# Dual-MCU-control-board.net
KiCad netlist of a schematic drawn in Altium Designer
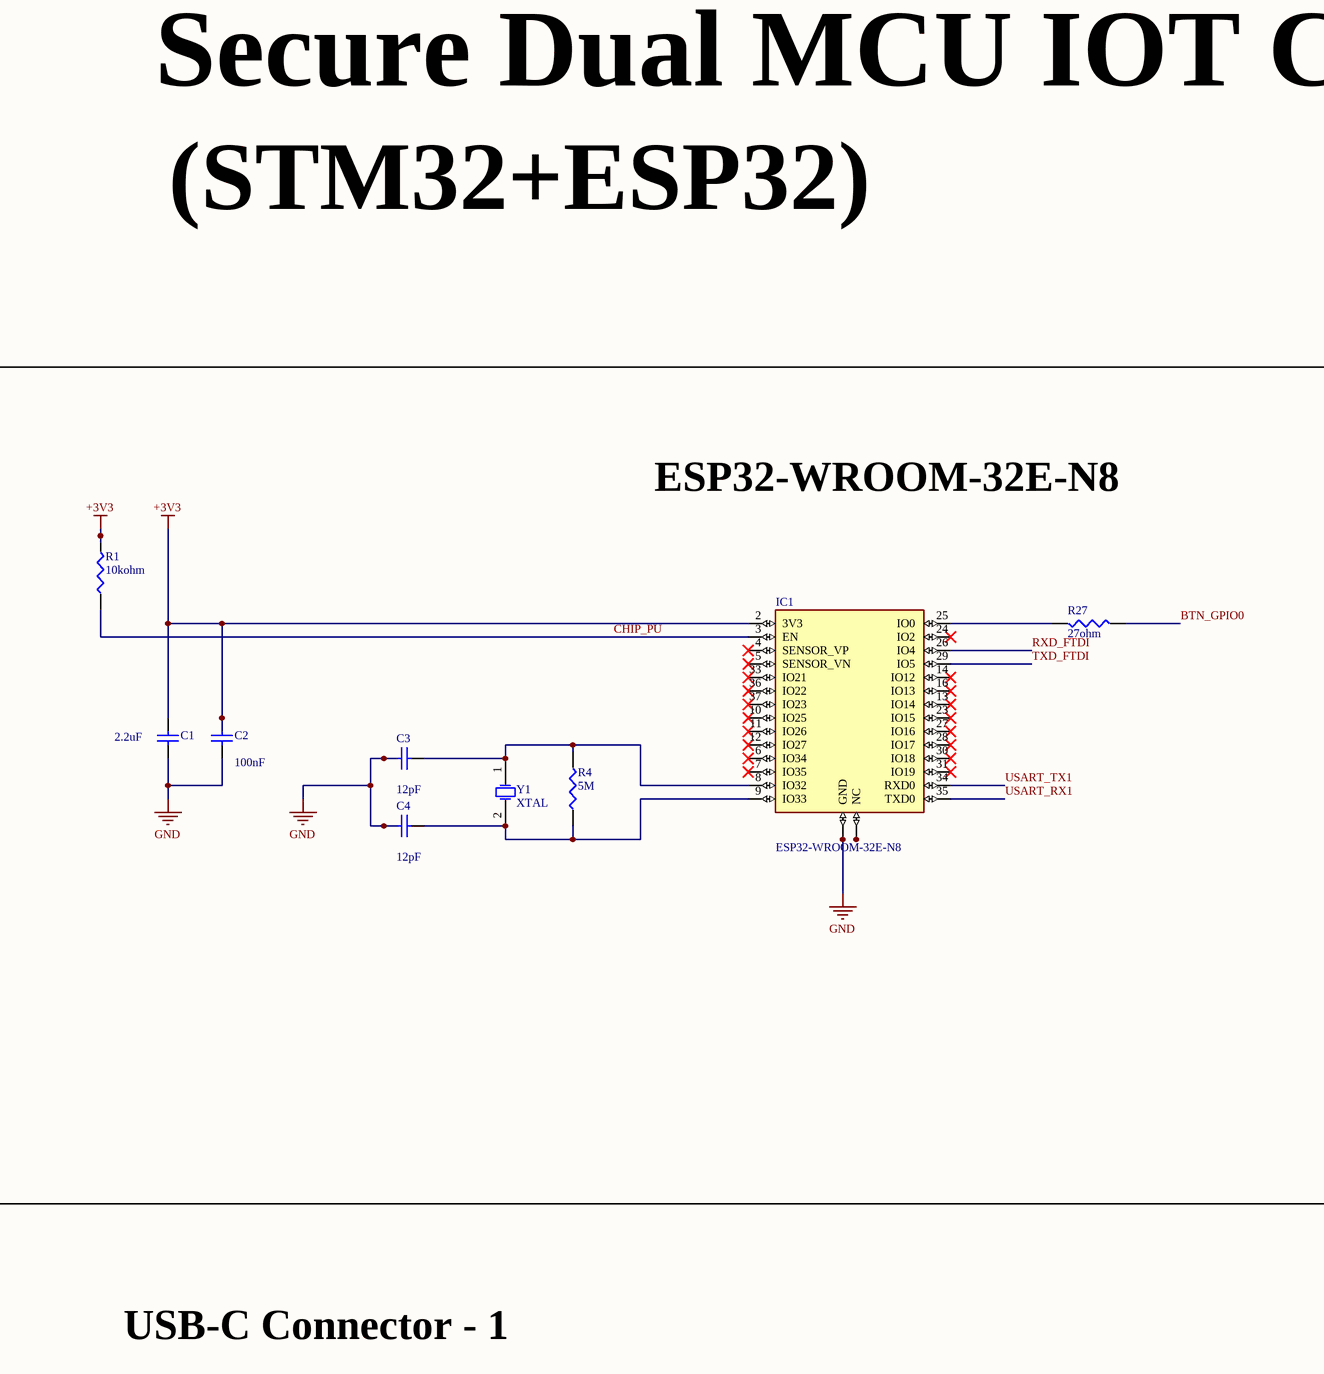
[diagram p0: Dual-MCU-control-board.SchDoc, top left]
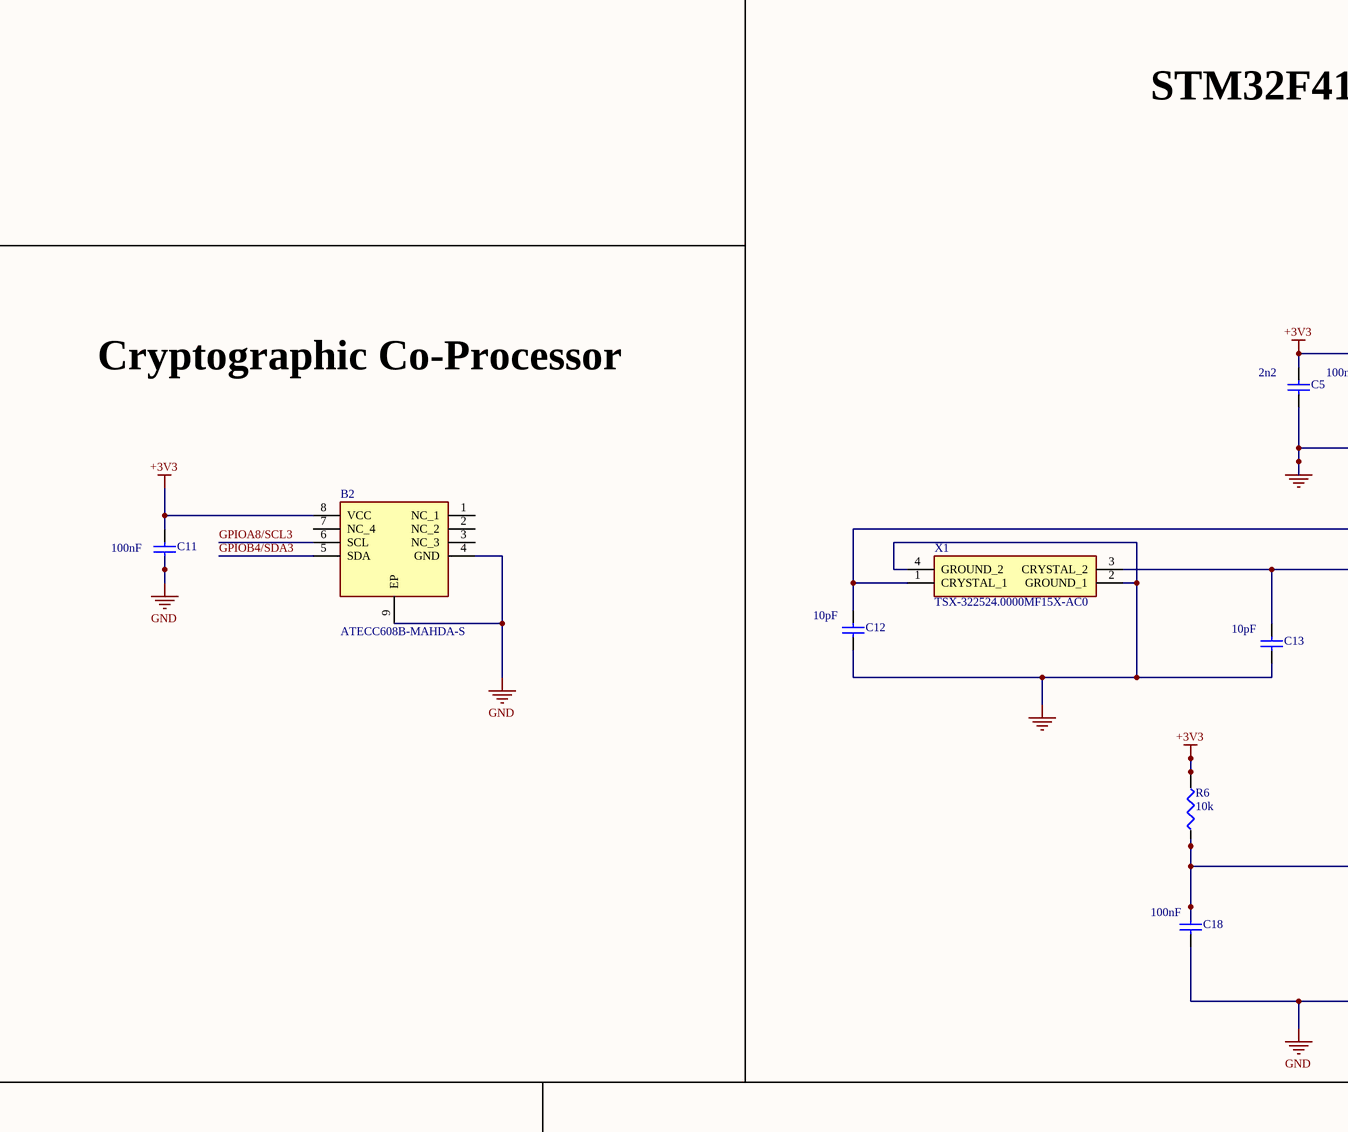
[diagram p1: Dual-MCU-control-board.SchDoc, top middle]
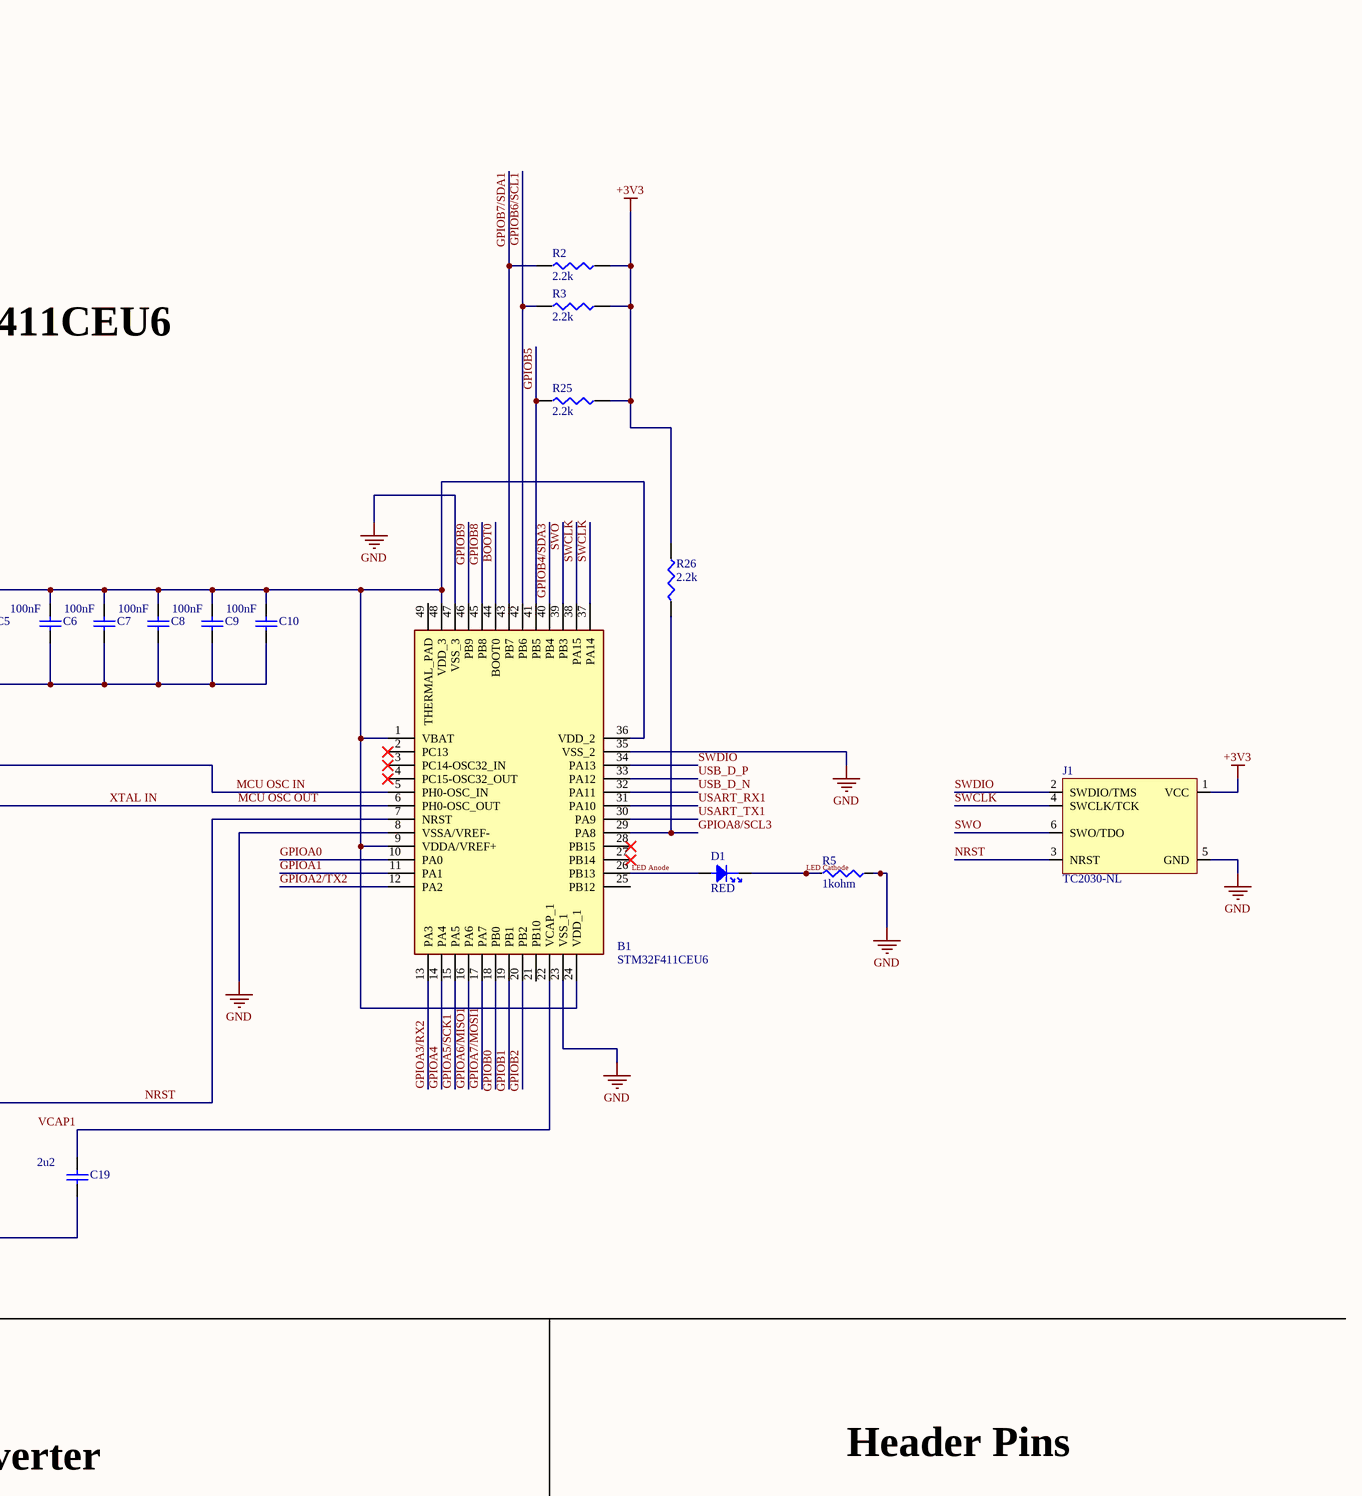
[diagram p2: Dual-MCU-control-board.SchDoc, top right]
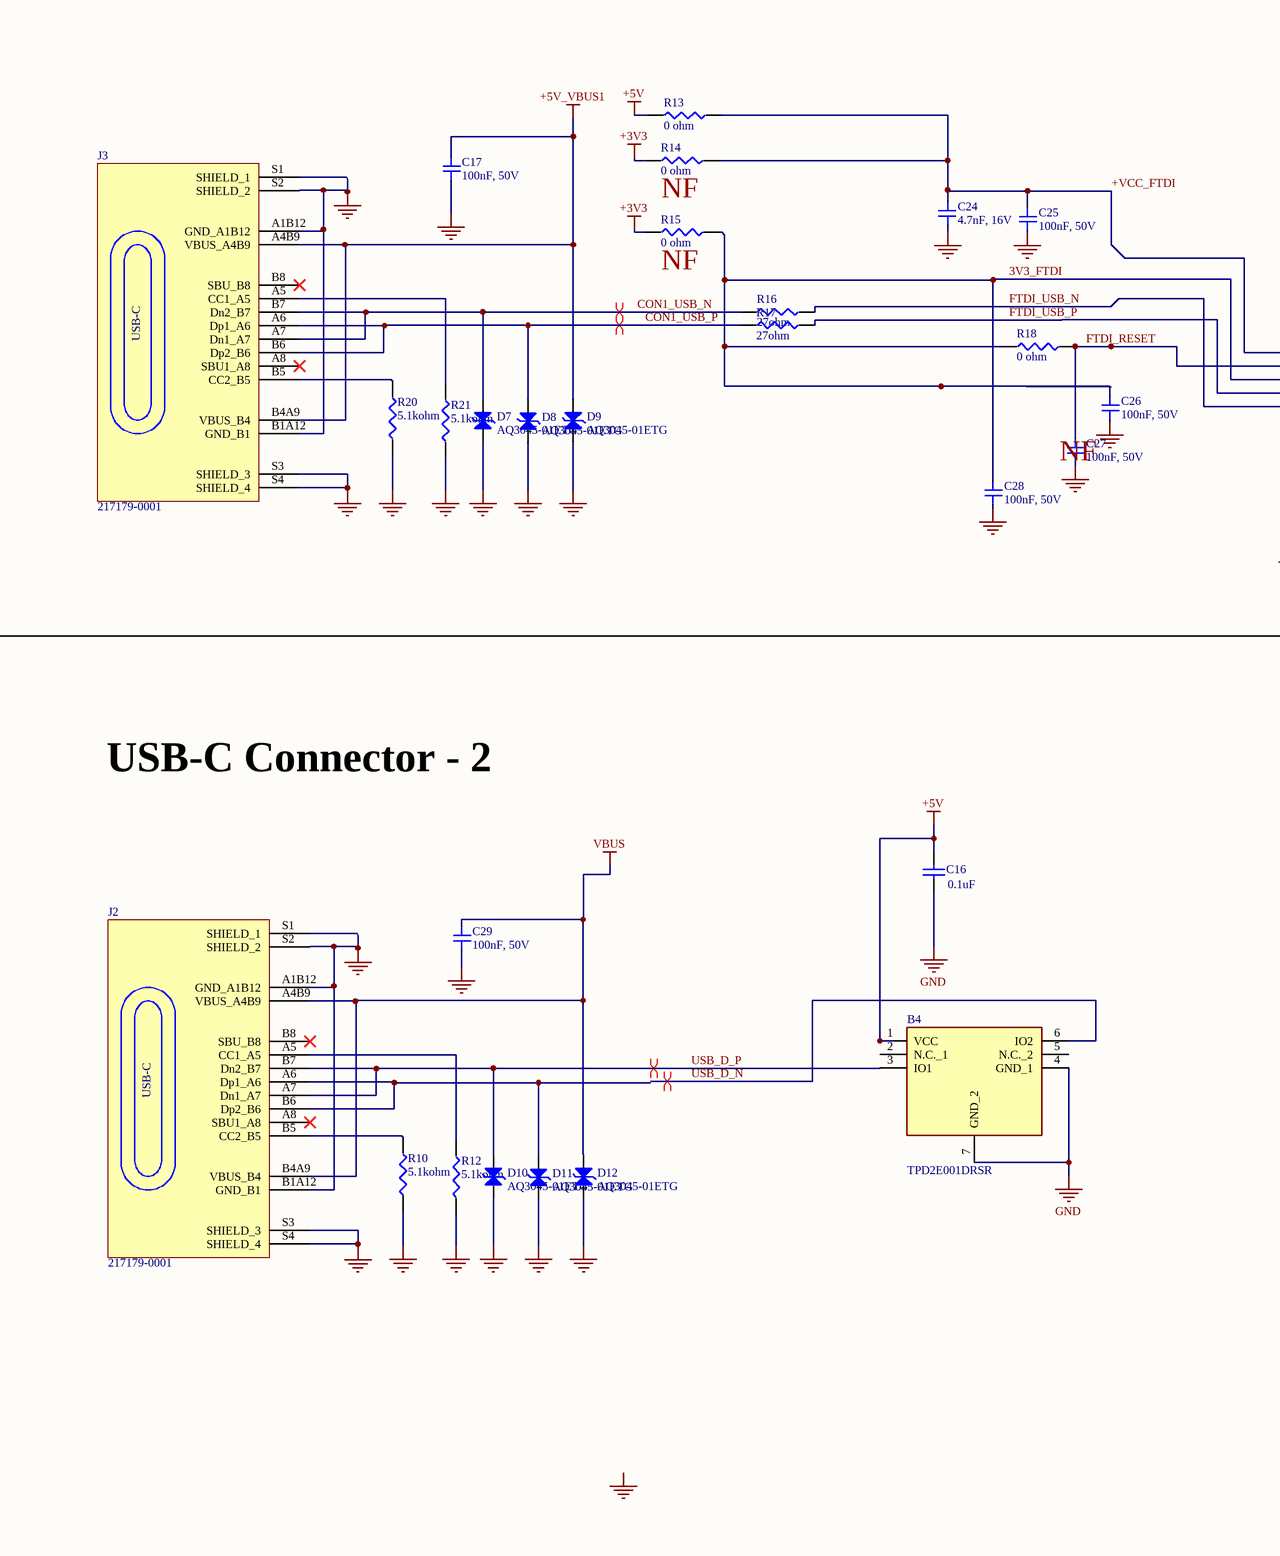
[diagram p3: Dual-MCU-control-board.SchDoc, bottom left]
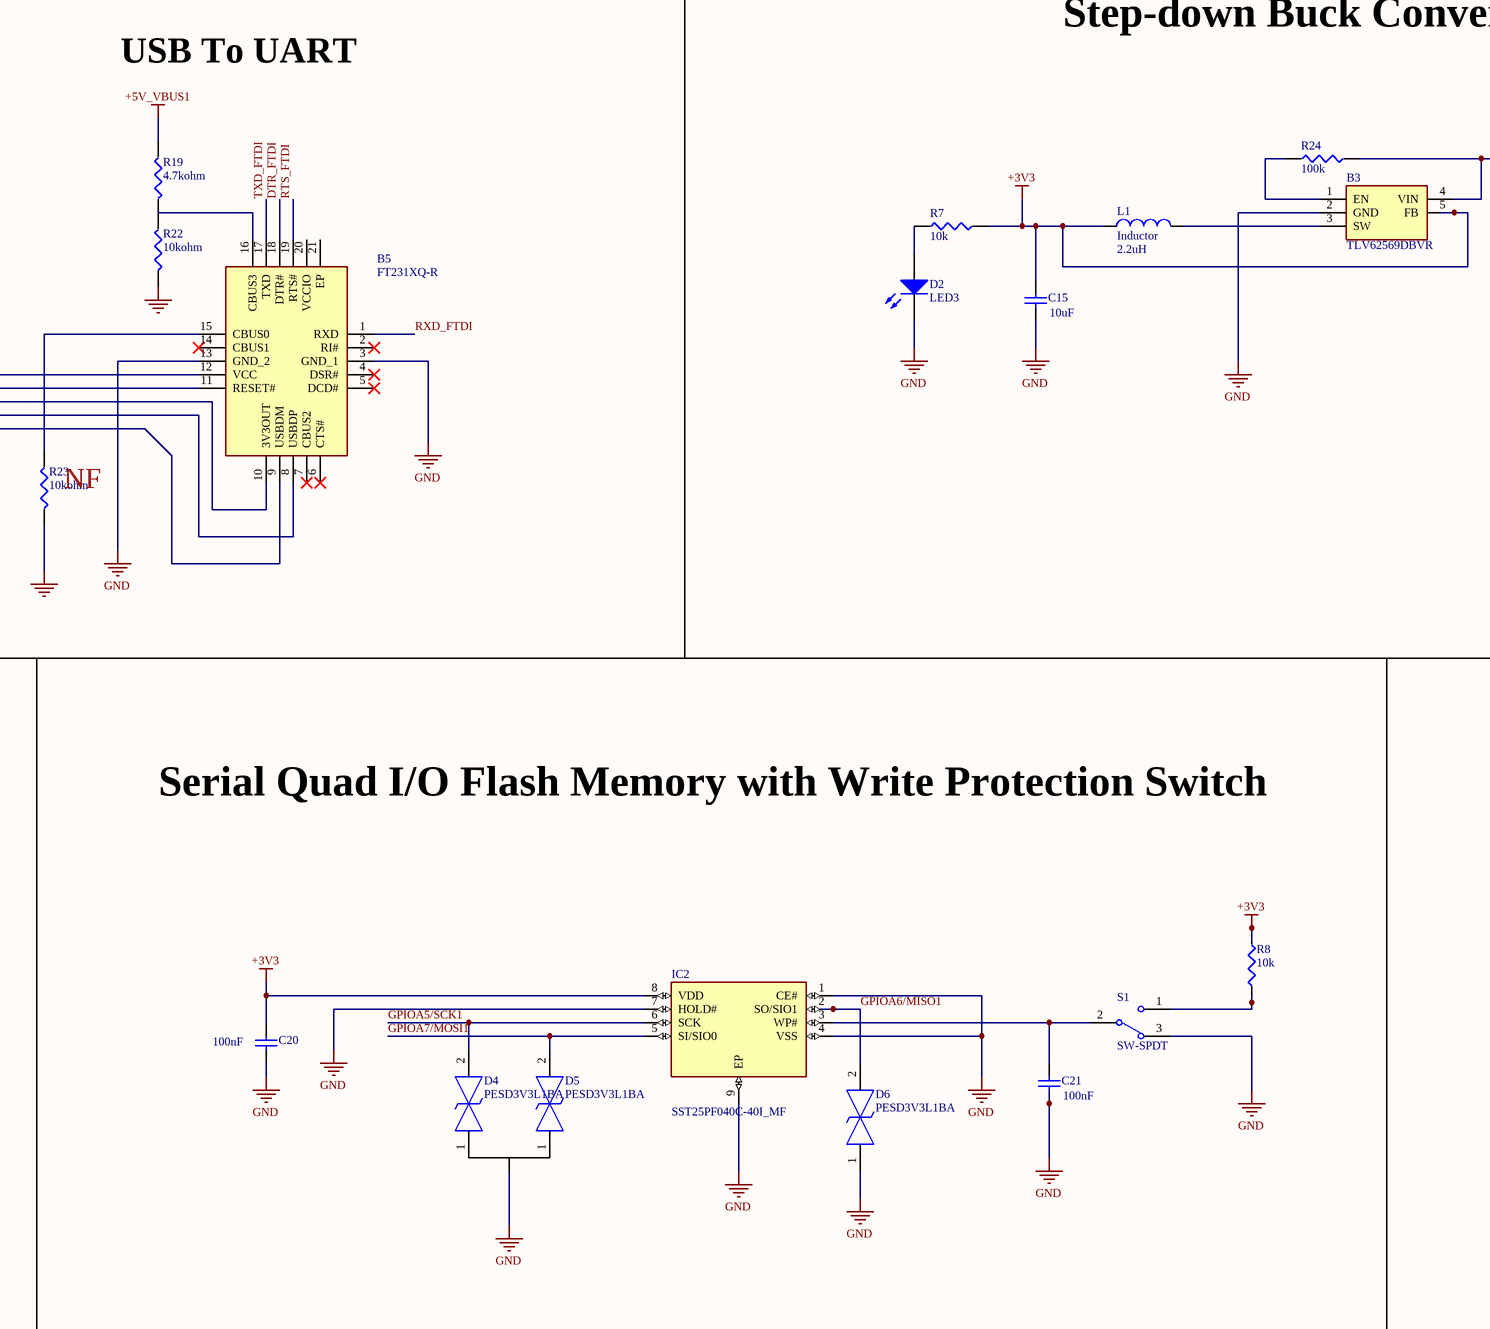
[diagram p4: Dual-MCU-control-board.SchDoc, bottom middle]
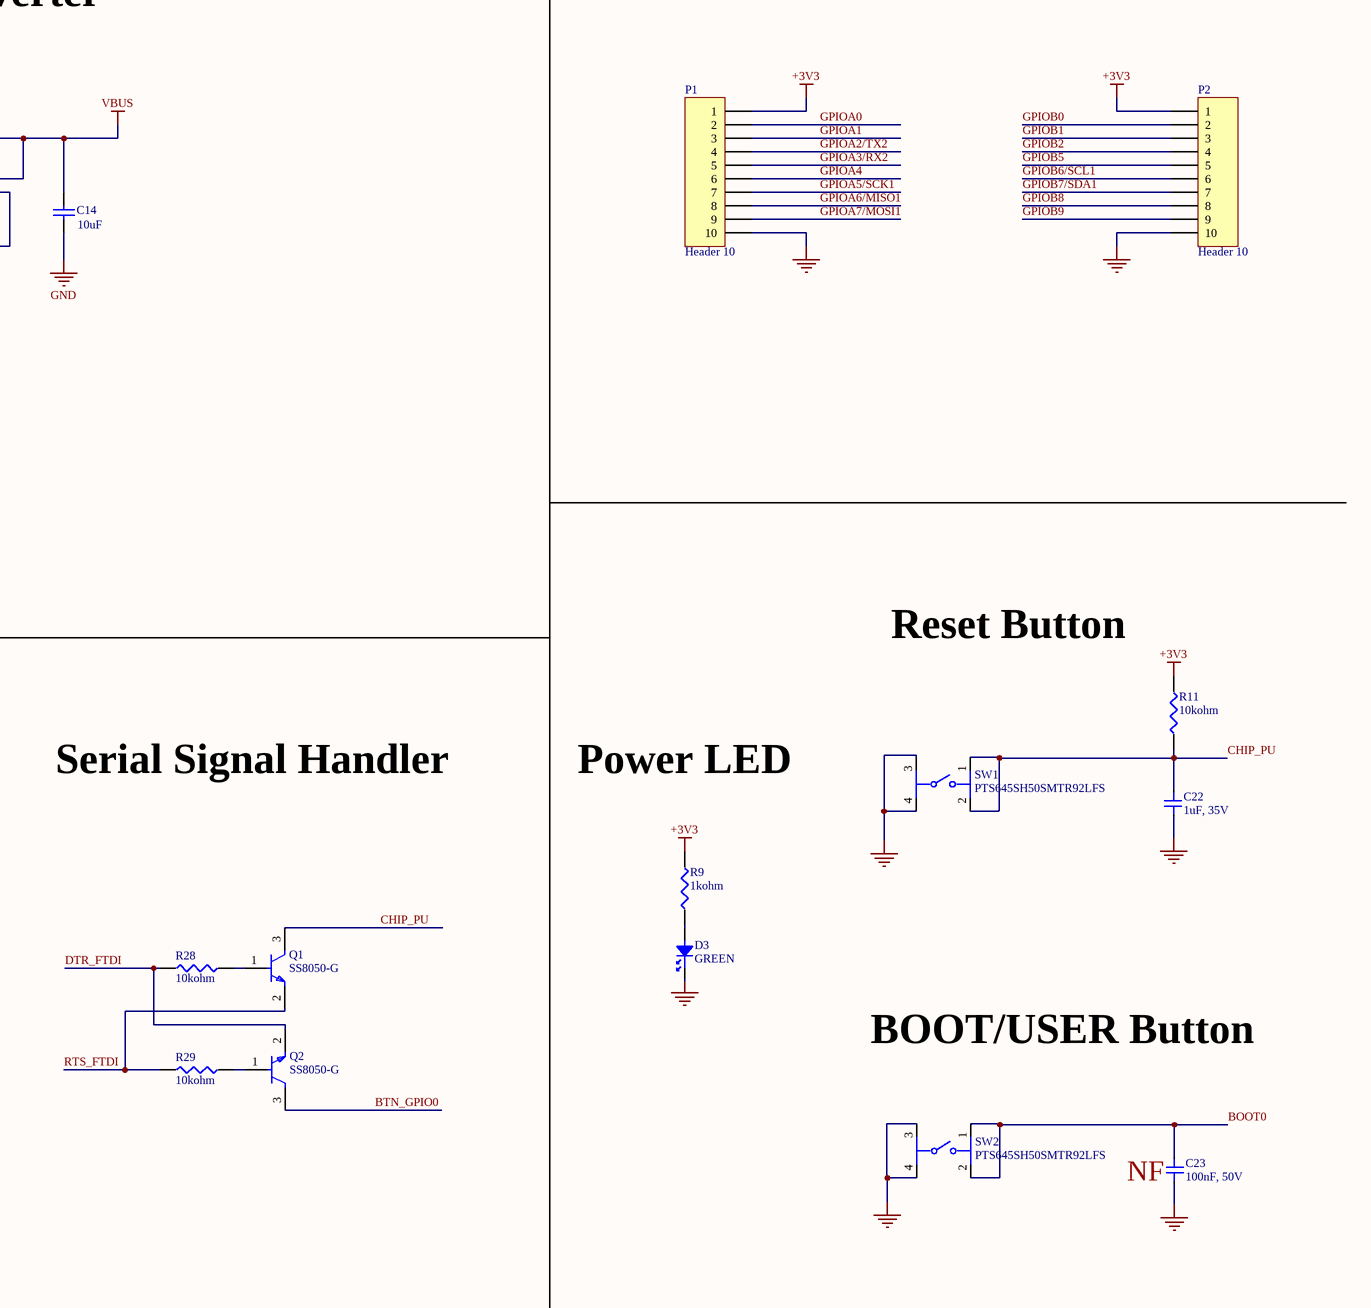
[diagram p5: Dual-MCU-control-board.SchDoc, bottom right]

(export (version "E")
  (design (tool "Eeschema 10.0.6"))
  (components
    (comp (ref "B1")
      (value "STM32F411CEU6")
      (footprint "QFN50P700X700X60-49N-D")
      (fields (field (name "MOUSER PART NUMBER") "511-STM32F411CEU6"))
      (libsource (lib "STM32F411CEU6") (part "STM32F411CEU6"))
    )
    (comp (ref "B2")
      (value "ATECC608B-MAHDA-S")
      (footprint "SON50P300X200X60-9N")
      (description "Security ICs / Authentication ICs ECC/ECDH, I2C, small 3K reel UDFN")
      (fields (field (name "MOUSER PART NUMBER") "579-TECC608B-MAHDA-S"))
      (libsource (lib "ATECC608B-MAHDA-S") (part "ATECC608B-MAHDA-S"))
    )
    (comp (ref "B3")
      (value "TLV62569DBVR")
      (footprint "SOT95P280X145-5N")
      (description "2.5V-5.5V input, 2-A high efficiency step-down buck converter in SOT23 and SOT563 package")
      (fields (field (name "MOUSER PART NUMBER") "595-TLV62569DBVR"))
      (libsource (lib "TLV62569DBVR") (part "TLV62569DBVR"))
    )
    (comp (ref "B4")
      (value "TPD2E001DRSR")
      (footprint "SON95P300X300X80-7N-D")
      (description "TPD2E001 LOW-CAPACITANCE 2-CHANNEL +/-15-kV ESD-PROTECTION ARRAY FOR HIGH-SPEED DATA INTERFACES")
      (fields (field (name "MOUSER PART NUMBER") "595-TPD2E001DRSR"))
      (libsource (lib "TPD2E001DRSR") (part "TPD2E001DRSR"))
    )
    (comp (ref "B5")
      (value "FT231XQ-R")
      (footprint "QFN50P400X400X80-21N")
      (description "FTDI Chip FT231XQ-R, USB Transceiver")
      (fields (field (name "MOUSER PART NUMBER") "895-FT231XQ-R"))
      (libsource (lib "FT231XQ-R") (part "FT231XQ-R"))
    )
    (comp (ref "C1")
      (value "2.2uF")
      (footprint "C1206")
      (description "Capacitor (Semiconductor SIM Model)")
      (fields (field (name "Comment") "Cap Semi") (field (name "PUBLISHER") "Altium Limited"))
      (libsource (lib "Miscellaneous Devices") (part "Cap Semi"))
    )
    (comp (ref "C2")
      (value "100nF")
      (footprint "C1206")
      (description "Capacitor (Semiconductor SIM Model)")
      (fields (field (name "Comment") "Cap Semi") (field (name "PUBLISHER") "Altium Limited"))
      (libsource (lib "Miscellaneous Devices") (part "Cap Semi"))
    )
    (comp (ref "C3")
      (value "12pF")
      (footprint "C1206")
      (description "Capacitor (Semiconductor SIM Model)")
      (fields (field (name "Comment") "Cap Semi") (field (name "PUBLISHER") "Altium Limited"))
      (libsource (lib "Miscellaneous Devices") (part "Cap Semi"))
    )
    (comp (ref "C4")
      (value "12pF")
      (footprint "C1206")
      (description "Capacitor (Semiconductor SIM Model)")
      (fields (field (name "Comment") "Cap Semi") (field (name "PUBLISHER") "Altium Limited"))
      (libsource (lib "Miscellaneous Devices") (part "Cap Semi"))
    )
    (comp (ref "C5")
      (value "2n2")
      (footprint "C1206")
      (description "Capacitor (Semiconductor SIM Model)")
      (fields (field (name "Comment") "Cap Semi") (field (name "PUBLISHER") "Altium Limited"))
      (libsource (lib "Miscellaneous Devices") (part "Cap Semi"))
    )
    (comp (ref "C6")
      (value "100nF")
      (footprint "C1206")
      (description "Capacitor (Semiconductor SIM Model)")
      (fields (field (name "Comment") "Cap Semi") (field (name "PUBLISHER") "Altium Limited"))
      (libsource (lib "Miscellaneous Devices") (part "Cap Semi"))
    )
    (comp (ref "C7")
      (value "100nF")
      (footprint "C1206")
      (description "Capacitor (Semiconductor SIM Model)")
      (fields (field (name "Comment") "Cap Semi") (field (name "PUBLISHER") "Altium Limited"))
      (libsource (lib "Miscellaneous Devices") (part "Cap Semi"))
    )
    (comp (ref "C8")
      (value "100nF")
      (footprint "C1206")
      (description "Capacitor (Semiconductor SIM Model)")
      (fields (field (name "Comment") "Cap Semi") (field (name "PUBLISHER") "Altium Limited"))
      (libsource (lib "Miscellaneous Devices") (part "Cap Semi"))
    )
    (comp (ref "C9")
      (value "100nF")
      (footprint "C1206")
      (description "Capacitor (Semiconductor SIM Model)")
      (fields (field (name "Comment") "Cap Semi") (field (name "PUBLISHER") "Altium Limited"))
      (libsource (lib "Miscellaneous Devices") (part "Cap Semi"))
    )
    (comp (ref "C10")
      (value "100nF")
      (footprint "C1206")
      (description "Capacitor (Semiconductor SIM Model)")
      (fields (field (name "Comment") "Cap Semi") (field (name "PUBLISHER") "Altium Limited"))
      (libsource (lib "Miscellaneous Devices") (part "Cap Semi"))
    )
    (comp (ref "C11")
      (value "100nF")
      (footprint "C1206")
      (description "Capacitor (Semiconductor SIM Model)")
      (fields (field (name "Comment") "Cap Semi") (field (name "PUBLISHER") "Altium Limited"))
      (libsource (lib "Miscellaneous Devices") (part "Cap Semi"))
    )
    (comp (ref "C12")
      (value "10pF")
      (footprint "C1206")
      (description "Capacitor (Semiconductor SIM Model)")
      (fields (field (name "Comment") "Cap Semi") (field (name "PUBLISHER") "Altium Limited"))
      (libsource (lib "Miscellaneous Devices") (part "Cap Semi"))
    )
    (comp (ref "C13")
      (value "10pF")
      (footprint "C1206")
      (description "Capacitor (Semiconductor SIM Model)")
      (fields (field (name "Comment") "Cap Semi") (field (name "PUBLISHER") "Altium Limited"))
      (libsource (lib "Miscellaneous Devices") (part "Cap Semi"))
    )
    (comp (ref "C14")
      (value "10uF")
      (footprint "C1206")
      (description "Capacitor (Semiconductor SIM Model)")
      (fields (field (name "Comment") "Cap Semi") (field (name "PUBLISHER") "Altium Limited"))
      (libsource (lib "Miscellaneous Devices") (part "Cap Semi"))
    )
    (comp (ref "C15")
      (value "10uF")
      (footprint "C1206")
      (description "Capacitor (Semiconductor SIM Model)")
      (fields (field (name "Comment") "Cap Semi") (field (name "PUBLISHER") "Altium Limited"))
      (libsource (lib "Miscellaneous Devices") (part "Cap Semi"))
    )
    (comp (ref "C16")
      (value "0.1uF")
      (footprint "C1206")
      (description "Capacitor (Semiconductor SIM Model)")
      (fields (field (name "Comment") "Cap Semi") (field (name "PUBLISHER") "Altium Limited"))
      (libsource (lib "Miscellaneous Devices") (part "Cap Semi"))
    )
    (comp (ref "C17")
      (value "100nF, 50V")
      (footprint "CAPC1005X55N")
      (description "CAP CER 0.1UF 50V X7R 0402")
      (fields
        (field (name "MANUFACTURER") "Samsung")
        (field (name "MANUFACTURER PART NUMBER") "CL05B104KB54PNC")
      )
      (libsource (lib "Schlib") (part "CL05B104KB54PNC"))
    )
    (comp (ref "C18")
      (value "100nF")
      (footprint "C1206")
      (description "Capacitor (Semiconductor SIM Model)")
      (fields (field (name "Comment") "Cap Semi") (field (name "PUBLISHER") "Altium Limited"))
      (libsource (lib "Miscellaneous Devices") (part "Cap Semi"))
    )
    (comp (ref "C19")
      (value "2u2")
      (footprint "C1206")
      (description "Capacitor (Semiconductor SIM Model)")
      (fields (field (name "Comment") "Cap Semi") (field (name "PUBLISHER") "Altium Limited"))
      (libsource (lib "Miscellaneous Devices") (part "Cap Semi"))
    )
    (comp (ref "C20")
      (value "100nF")
      (footprint "C1206")
      (description "Capacitor (Semiconductor SIM Model)")
      (fields (field (name "Comment") "Cap Semi") (field (name "PUBLISHER") "Altium Limited"))
      (libsource (lib "Miscellaneous Devices") (part "Cap Semi"))
    )
    (comp (ref "C21")
      (value "100nF")
      (footprint "C1206")
      (description "Capacitor (Semiconductor SIM Model)")
      (fields (field (name "Comment") "Cap Semi") (field (name "PUBLISHER") "Altium Limited"))
      (libsource (lib "Miscellaneous Devices") (part "Cap Semi"))
    )
    (comp (ref "C22")
      (value "1uF, 35V")
      (footprint "CAPC1005X55N")
      (description "CAP CER 1UF 35V X5R 0402")
      (fields
        (field (name "MANUFACTURER") "Samsung")
        (field (name "MANUFACTURER PART NUMBER") "CL05A105KL5NRNC")
      )
      (libsource (lib "Schlib") (part "CL05A105KL5NRNC"))
    )
    (comp (ref "C23")
      (value "100nF, 50V")
      (footprint "CAPC1005X55N")
      (description "CAP CER 0.1UF 50V X7R 0402")
      (fields
        (field (name "MANUFACTURER") "Samsung")
        (field (name "MANUFACTURER PART NUMBER") "CL05B104KB54PNC")
      )
      (libsource (lib "Schlib") (part "CL05B104KB54PNC"))
    )
    (comp (ref "C24")
      (value "4.7nF, 16V")
      (footprint "CAPC1005X55N")
      (description "CAP CER 0402 4.7NF 16V X7R 10%")
      (fields
        (field (name "MANUFACTURER") "KEMET")
        (field (name "MANUFACTURER PART NUMBER") "C0402C472K4RECAUTO")
      )
      (libsource (lib "Schlib") (part "C0402C472K4RECAUTO"))
    )
    (comp (ref "C25")
      (value "100nF, 50V")
      (footprint "CAPC1005X55N")
      (description "CAP CER 0.1UF 50V X7R 0402")
      (fields
        (field (name "MANUFACTURER") "Samsung")
        (field (name "MANUFACTURER PART NUMBER") "CL05B104KB54PNC")
      )
      (libsource (lib "Schlib") (part "CL05B104KB54PNC"))
    )
    (comp (ref "C26")
      (value "100nF, 50V")
      (footprint "CAPC1005X55N")
      (description "CAP CER 0.1UF 50V X7R 0402")
      (fields
        (field (name "MANUFACTURER") "Samsung")
        (field (name "MANUFACTURER PART NUMBER") "CL05B104KB54PNC")
      )
      (libsource (lib "Schlib") (part "CL05B104KB54PNC"))
    )
    (comp (ref "C27")
      (value "100nF, 50V")
      (footprint "CAPC1005X55N")
      (description "CAP CER 0.1UF 50V X7R 0402")
      (fields
        (field (name "MANUFACTURER") "Samsung")
        (field (name "MANUFACTURER PART NUMBER") "CL05B104KB54PNC")
      )
      (libsource (lib "Schlib") (part "CL05B104KB54PNC"))
    )
    (comp (ref "C28")
      (value "100nF, 50V")
      (footprint "CAPC1005X55N")
      (description "CAP CER 0.1UF 50V X7R 0402")
      (fields
        (field (name "MANUFACTURER") "Samsung")
        (field (name "MANUFACTURER PART NUMBER") "CL05B104KB54PNC")
      )
      (libsource (lib "Schlib") (part "CL05B104KB54PNC"))
    )
    (comp (ref "C29")
      (value "100nF, 50V")
      (footprint "CAPC1005X55N")
      (description "CAP CER 0.1UF 50V X7R 0402")
      (fields
        (field (name "MANUFACTURER") "Samsung")
        (field (name "MANUFACTURER PART NUMBER") "CL05B104KB54PNC")
      )
      (libsource (lib "Schlib") (part "CL05B104KB54PNC"))
    )
    (comp (ref "D1")
      (value "RED")
      (footprint "LEDC1005X35N")
      (description "Single Color LED, Super Red, 0.5mm")
      (fields
        (field (name "MANUFACTURER") "Vishay")
        (field (name "MANUFACTURER PART NUMBER") "VLMS1500-GS08")
      )
      (libsource (lib "Schlib") (part "VLMS1500-GS08"))
    )
    (comp (ref "D2")
      (value "LED3")
      (footprint "3.5X2.8X1.9")
      (description "Typical BLUE SiC LED")
      (fields (field (name "PUBLISHER") "Altium Limited"))
      (libsource (lib "Miscellaneous Devices") (part "LED3"))
    )
    (comp (ref "D3")
      (value "GREEN")
      (footprint "LEDC1005X35N")
      (description "Single Color LED, Yellow Green, 0.5mm")
      (fields
        (field (name "MANUFACTURER") "Vishay")
        (field (name "MANUFACTURER PART NUMBER") "VLMG1500-GS08")
      )
      (libsource (lib "Schlib") (part "VLMG1500-GS08"))
    )
    (comp (ref "D4")
      (value "PESD3V3L1BA")
      (footprint "SOD2512X110N")
      (description "TVS Diode Bi-Directional PESD3V3L1BA 26V, 500W, UMD 2-Pin")
      (libsource (lib "PESD3V3L1BA") (part "PESD3V3L1BA"))
    )
    (comp (ref "D5")
      (value "PESD3V3L1BA")
      (footprint "SOD2512X110N")
      (description "TVS Diode Bi-Directional PESD3V3L1BA 26V, 500W, UMD 2-Pin")
      (libsource (lib "PESD3V3L1BA") (part "PESD3V3L1BA"))
    )
    (comp (ref "D6")
      (value "PESD3V3L1BA")
      (footprint "SOD2512X110N")
      (description "TVS Diode Bi-Directional PESD3V3L1BA 26V, 500W, UMD 2-Pin")
      (libsource (lib "PESD3V3L1BA") (part "PESD3V3L1BA"))
    )
    (comp (ref "D7")
      (value "AQ3045-01ETG")
      (footprint "SOD882")
      (description "TVS DIODE 5.3VWM 12VC SOD882")
      (fields (field (name "MANUFACTURER") "Littelfuse") (field (name "LCSC PART NUMBER") "C3710326"))
      (libsource (lib "Schlib") (part "AQ3045-01ETG"))
    )
    (comp (ref "D8")
      (value "AQ3045-01ETG")
      (footprint "SOD882")
      (description "TVS DIODE 5.3VWM 12VC SOD882")
      (fields (field (name "MANUFACTURER") "Littelfuse") (field (name "LCSC PART NUMBER") "C3710326"))
      (libsource (lib "Schlib") (part "AQ3045-01ETG"))
    )
    (comp (ref "D9")
      (value "AQ3045-01ETG")
      (footprint "SOD882")
      (description "TVS DIODE 5.3VWM 12VC SOD882")
      (fields (field (name "MANUFACTURER") "Littelfuse") (field (name "LCSC PART NUMBER") "C3710326"))
      (libsource (lib "Schlib") (part "AQ3045-01ETG"))
    )
    (comp (ref "D10")
      (value "AQ3045-01ETG")
      (footprint "SOD882")
      (description "TVS DIODE 5.3VWM 12VC SOD882")
      (fields (field (name "MANUFACTURER") "Littelfuse") (field (name "LCSC PART NUMBER") "C3710326"))
      (libsource (lib "Schlib") (part "AQ3045-01ETG"))
    )
    (comp (ref "D11")
      (value "AQ3045-01ETG")
      (footprint "SOD882")
      (description "TVS DIODE 5.3VWM 12VC SOD882")
      (fields (field (name "MANUFACTURER") "Littelfuse") (field (name "LCSC PART NUMBER") "C3710326"))
      (libsource (lib "Schlib") (part "AQ3045-01ETG"))
    )
    (comp (ref "D12")
      (value "AQ3045-01ETG")
      (footprint "SOD882")
      (description "TVS DIODE 5.3VWM 12VC SOD882")
      (fields (field (name "MANUFACTURER") "Littelfuse") (field (name "LCSC PART NUMBER") "C3710326"))
      (libsource (lib "Schlib") (part "AQ3045-01ETG"))
    )
    (comp (ref "IC1")
      (value "ESP32-WROOM-32E-N8")
      (footprint "ESP32WROOM32EN8")
      (fields (field (name "MF") "Espressif Systems"))
      (libsource (lib "ESP32-WROOM-32E-N8") (part "ESP32-WROOM-32E-N8"))
    )
    (comp (ref "IC2")
      (value "SST25PF040C-40I_MF")
      (footprint "SON127P600X500X80-9N")
      (description "FLASH Memory IC 4Mb (512K x 8) SPI 40 MHz 8-WDFN (5x6)")
      (fields (field (name "MF") "Microchip") (field (name "MP") "SST25PF040C-40I/MF"))
      (libsource (lib "SST25PF040C-40I_MF") (part "SST25PF040C-40I_MF"))
    )
    (comp (ref "J1")
      (value "TC2030-NL")
      (footprint "TC2030-NL-FP")
      (description "Tag-Connect No-Solder SWD Debug Connector (No Legs) DO NOT PLACE")
      (fields
        (field (name "MANUFACTURER") "Tag-Connect")
        (field (name "MANUFACTURER PART NUMBER") "TC2030-NL-FP")
      )
      (libsource (lib "Schematic-Lib-PhilsLab") (part "TC2030-NL"))
    )
    (comp (ref "J2")
      (value "217179-0001")
      (footprint "FP-2171790001-MFG")
      (description "CONN RCP USB2.0 TYP C 24P SMD RA")
      (fields (field (name "MANUFACTURER") "Molex"))
      (libsource (lib "Schlib") (part "217179-0001"))
    )
    (comp (ref "J3")
      (value "217179-0001")
      (footprint "FP-2171790001-MFG")
      (description "CONN RCP USB2.0 TYP C 24P SMD RA")
      (fields (field (name "MANUFACTURER") "Molex"))
      (libsource (lib "Schlib") (part "217179-0001"))
    )
    (comp (ref "L1")
      (value "Inductor")
      (footprint "0402-A")
      (fields (field (name "ALTIUM_VALUE") "2.2uH") (field (name "PUBLISHER") "Altium Limited"))
      (libsource (lib "Miscellaneous Devices") (part "Inductor"))
    )
    (comp (ref "P1")
      (value "Header 10")
      (footprint "HDR1X10")
      (description "Header, 10-Pin")
      (fields (field (name "PUBLISHER") "Altium Limited"))
      (libsource (lib "") (part "Header 10_1"))
    )
    (comp (ref "P2")
      (value "Header 10")
      (footprint "HDR1X10")
      (description "Header, 10-Pin")
      (fields (field (name "PUBLISHER") "Altium Limited"))
      (libsource (lib "Miscellaneous Connectors") (part "Header 10"))
    )
    (comp (ref "Q1")
      (value "SS8050-G")
      (footprint "FP-SS8050-G-IPC_B")
      (description "TRANS NPN 25V 1.5A SOT-23-3")
      (fields (field (name "MANUFACTURER") "Comchip") (field (name "LCSC PART NUMBER") "C164886"))
      (libsource (lib "Schlib") (part "SS8050-G"))
    )
    (comp (ref "Q2")
      (value "SS8050-G")
      (footprint "FP-SS8050-G-IPC_B")
      (description "TRANS NPN 25V 1.5A SOT-23-3")
      (fields (field (name "MANUFACTURER") "Comchip") (field (name "LCSC PART NUMBER") "C164886"))
      (libsource (lib "Schlib") (part "SS8050-G"))
    )
    (comp (ref "R1")
      (value "10kohm")
      (footprint "RESC1005X37N")
      (description "RES 10K OHM 1% 1/16W 0402")
      (fields
        (field (name "MANUFACTURER") "Yageo")
        (field (name "MANUFACTURER PART NUMBER") "RC0402FR-07100KL")
      )
      (libsource (lib "Schlib") (part "RC0402FR-07100KL"))
    )
    (comp (ref "R2")
      (value "2.2k")
      (footprint "RESC1005X37N")
      (description "RES 1K OHM 1% 1/16W 0402")
      (fields
        (field (name "MANUFACTURER") "Yageo")
        (field (name "MANUFACTURER PART NUMBER") "RC0402FR-071KL")
      )
      (libsource (lib "Schlib") (part "RC0402FR-071KL"))
    )
    (comp (ref "R3")
      (value "2.2k")
      (footprint "RESC1005X37N")
      (description "RES 1K OHM 1% 1/16W 0402")
      (fields
        (field (name "MANUFACTURER") "Yageo")
        (field (name "MANUFACTURER PART NUMBER") "RC0402FR-071KL")
      )
      (libsource (lib "Schlib") (part "RC0402FR-071KL"))
    )
    (comp (ref "R4")
      (value "5M")
      (footprint "RESC1005X37N")
      (description "RES 4.7K OHM 1% 1/16W 0402")
      (fields
        (field (name "MANUFACTURER") "Yageo")
        (field (name "MANUFACTURER PART NUMBER") "RC0402FR-074K7L")
      )
      (libsource (lib "Schlib") (part "RC0402FR-074K7L"))
    )
    (comp (ref "R5")
      (value "1kohm")
      (footprint "RESC1005X37N")
      (description "RES 1K OHM 1% 1/16W 0402")
      (fields
        (field (name "MANUFACTURER") "Yageo")
        (field (name "MANUFACTURER PART NUMBER") "RC0402FR-071KL")
      )
      (libsource (lib "Schlib") (part "RC0402FR-071KL"))
    )
    (comp (ref "R6")
      (value "10k")
      (footprint "RESC1005X37N")
      (description "RES 1K OHM 1% 1/16W 0402")
      (fields
        (field (name "MANUFACTURER") "Yageo")
        (field (name "MANUFACTURER PART NUMBER") "RC0402FR-071KL")
      )
      (libsource (lib "Schlib") (part "RC0402FR-071KL"))
    )
    (comp (ref "R7")
      (value "10k")
      (footprint "RESC1005X37N")
      (description "RES 1K OHM 1% 1/16W 0402")
      (fields
        (field (name "MANUFACTURER") "Yageo")
        (field (name "MANUFACTURER PART NUMBER") "RC0402FR-071KL")
      )
      (libsource (lib "Schlib") (part "RC0402FR-071KL"))
    )
    (comp (ref "R8")
      (value "10k")
      (footprint "RESC1005X37N")
      (description "RES 1K OHM 1% 1/16W 0402")
      (fields
        (field (name "MANUFACTURER") "Yageo")
        (field (name "MANUFACTURER PART NUMBER") "RC0402FR-071KL")
      )
      (libsource (lib "Schlib") (part "RC0402FR-071KL"))
    )
    (comp (ref "R9")
      (value "1kohm")
      (footprint "RESC1005X37N")
      (description "RES 1K OHM 1% 1/16W 0402")
      (fields
        (field (name "MANUFACTURER") "Yageo")
        (field (name "MANUFACTURER PART NUMBER") "RC0402FR-071KL")
      )
      (libsource (lib "Schlib") (part "RC0402FR-071KL"))
    )
    (comp (ref "R10")
      (value "5.1kohm")
      (footprint "RESC1005X37N")
      (description "RES 5.1K OHM 1% 1/16W 0402")
      (fields
        (field (name "MANUFACTURER") "Yageo")
        (field (name "MANUFACTURER PART NUMBER") "RC0402FR-075K1L")
      )
      (libsource (lib "Schlib") (part "RC0402FR-075K1L"))
    )
    (comp (ref "R11")
      (value "10kohm")
      (footprint "RESC1005X37N")
      (description "RES SMD 10K OHM 1% 1/16W 0402")
      (fields
        (field (name "MANUFACTURER") "Yageo")
        (field (name "MANUFACTURER PART NUMBER") "AC0402FR-0710KL")
      )
      (libsource (lib "Schlib") (part "AC0402FR-0710KL"))
    )
    (comp (ref "R12")
      (value "5.1kohm")
      (footprint "RESC1005X37N")
      (description "RES 5.1K OHM 1% 1/16W 0402")
      (fields
        (field (name "MANUFACTURER") "Yageo")
        (field (name "MANUFACTURER PART NUMBER") "RC0402FR-075K1L")
      )
      (libsource (lib "Schlib") (part "RC0402FR-075K1L"))
    )
    (comp (ref "R13")
      (value "0 ohm")
      (footprint "RESC1005X37N")
      (description "RES 0 OHM JUMPER 1/16W 0402")
      (fields
        (field (name "MANUFACTURER") "Yageo")
        (field (name "MANUFACTURER PART NUMBER") "RC0402JR-070RL")
      )
      (libsource (lib "Schlib") (part "RC0402JR-070RL"))
    )
    (comp (ref "R14")
      (value "0 ohm")
      (footprint "RESC1005X37N")
      (description "RES 0 OHM JUMPER 1/16W 0402")
      (fields
        (field (name "MANUFACTURER") "Yageo")
        (field (name "MANUFACTURER PART NUMBER") "RC0402JR-070RL")
      )
      (libsource (lib "Schlib") (part "RC0402JR-070RL"))
    )
    (comp (ref "R15")
      (value "0 ohm")
      (footprint "RESC1005X37N")
      (description "RES 0 OHM JUMPER 1/16W 0402")
      (fields
        (field (name "MANUFACTURER") "Yageo")
        (field (name "MANUFACTURER PART NUMBER") "RC0402JR-070RL")
      )
      (libsource (lib "Schlib") (part "RC0402JR-070RL"))
    )
    (comp (ref "R16")
      (value "27ohm")
      (footprint "RESC1005X37N")
      (description "RES 27 OHM 1% 1/16W 0402")
      (fields
        (field (name "MANUFACTURER") "Yageo")
        (field (name "MANUFACTURER PART NUMBER") "RC0402FR-0727RL")
      )
      (libsource (lib "Schlib") (part "RC0402FR-0727RL"))
    )
    (comp (ref "R17")
      (value "27ohm")
      (footprint "RESC1005X37N")
      (description "RES 27 OHM 1% 1/16W 0402")
      (fields
        (field (name "MANUFACTURER") "Yageo")
        (field (name "MANUFACTURER PART NUMBER") "RC0402FR-0727RL")
      )
      (libsource (lib "Schlib") (part "RC0402FR-0727RL"))
    )
    (comp (ref "R18")
      (value "0 ohm")
      (footprint "RESC1005X37N")
      (description "RES 0 OHM JUMPER 1/16W 0402")
      (fields
        (field (name "MANUFACTURER") "Yageo")
        (field (name "MANUFACTURER PART NUMBER") "RC0402JR-070RL")
      )
      (libsource (lib "Schlib") (part "RC0402JR-070RL"))
    )
    (comp (ref "R19")
      (value "4.7kohm")
      (footprint "RESC1005X37N")
      (description "RES 4.7K OHM 1% 1/16W 0402")
      (fields
        (field (name "MANUFACTURER") "Yageo")
        (field (name "MANUFACTURER PART NUMBER") "RC0402FR-074K7L")
      )
      (libsource (lib "Schlib") (part "RC0402FR-074K7L"))
    )
    (comp (ref "R20")
      (value "5.1kohm")
      (footprint "RESC1005X37N")
      (description "RES 5.1K OHM 1% 1/16W 0402")
      (fields
        (field (name "MANUFACTURER") "Yageo")
        (field (name "MANUFACTURER PART NUMBER") "RC0402FR-075K1L")
      )
      (libsource (lib "Schlib") (part "RC0402FR-075K1L"))
    )
    (comp (ref "R21")
      (value "5.1kohm")
      (footprint "RESC1005X37N")
      (description "RES 5.1K OHM 1% 1/16W 0402")
      (fields
        (field (name "MANUFACTURER") "Yageo")
        (field (name "MANUFACTURER PART NUMBER") "RC0402FR-075K1L")
      )
      (libsource (lib "Schlib") (part "RC0402FR-075K1L"))
    )
    (comp (ref "R22")
      (value "10kohm")
      (footprint "RESC1005X37N")
      (description "RES SMD 10K OHM 1% 1/16W 0402")
      (fields
        (field (name "MANUFACTURER") "Yageo")
        (field (name "MANUFACTURER PART NUMBER") "AC0402FR-0710KL")
      )
      (libsource (lib "Schlib") (part "AC0402FR-0710KL"))
    )
    (comp (ref "R23")
      (value "10kohm")
      (footprint "RESC1005X37N")
      (description "RES SMD 10K OHM 1% 1/16W 0402")
      (fields
        (field (name "MANUFACTURER") "Yageo")
        (field (name "MANUFACTURER PART NUMBER") "AC0402FR-0710KL")
      )
      (libsource (lib "Schlib") (part "AC0402FR-0710KL"))
    )
    (comp (ref "R24")
      (value "100k")
      (footprint "RESC1005X37N")
      (description "RES 1K OHM 1% 1/16W 0402")
      (fields
        (field (name "MANUFACTURER") "Yageo")
        (field (name "MANUFACTURER PART NUMBER") "RC0402FR-071KL")
      )
      (libsource (lib "Schlib") (part "RC0402FR-071KL"))
    )
    (comp (ref "R25")
      (value "2.2k")
      (footprint "RESC1005X37N")
      (description "RES 1K OHM 1% 1/16W 0402")
      (fields
        (field (name "MANUFACTURER") "Yageo")
        (field (name "MANUFACTURER PART NUMBER") "RC0402FR-071KL")
      )
      (libsource (lib "Schlib") (part "RC0402FR-071KL"))
    )
    (comp (ref "R26")
      (value "2.2k")
      (footprint "RESC1005X37N")
      (description "RES 1K OHM 1% 1/16W 0402")
      (fields
        (field (name "MANUFACTURER") "Yageo")
        (field (name "MANUFACTURER PART NUMBER") "RC0402FR-071KL")
      )
      (libsource (lib "Schlib") (part "RC0402FR-071KL"))
    )
    (comp (ref "R27")
      (value "27ohm")
      (footprint "RESC1005X37N")
      (description "RES 27 OHM 1% 1/16W 0402")
      (fields
        (field (name "MANUFACTURER") "Yageo")
        (field (name "MANUFACTURER PART NUMBER") "RC0402FR-0727RL")
      )
      (libsource (lib "Schlib") (part "RC0402FR-0727RL"))
    )
    (comp (ref "R28")
      (value "10kohm")
      (footprint "RESC1005X37N")
      (description "RES SMD 10K OHM 1% 1/16W 0402")
      (fields
        (field (name "MANUFACTURER") "Yageo")
        (field (name "MANUFACTURER PART NUMBER") "AC0402FR-0710KL")
      )
      (libsource (lib "Schlib") (part "AC0402FR-0710KL"))
    )
    (comp (ref "R29")
      (value "10kohm")
      (footprint "RESC1005X37N")
      (description "RES SMD 10K OHM 1% 1/16W 0402")
      (fields
        (field (name "MANUFACTURER") "Yageo")
        (field (name "MANUFACTURER PART NUMBER") "AC0402FR-0710KL")
      )
      (libsource (lib "Schlib") (part "AC0402FR-0710KL"))
    )
    (comp (ref "S1")
      (value "SW-SPDT")
      (footprint "TL36WW15050")
      (description "SPDT Subminiature Toggle Switch, Right Angle Mounting, Vertical Actuation")
      (fields (field (name "PUBLISHER") "Altium Limited"))
      (libsource (lib "Miscellaneous Devices") (part "SW-SPDT"))
    )
    (comp (ref "SW1")
      (value "PTS645SH50SMTR92LFS")
      (footprint "FP-PTS645SH50SMTR92LFS-MFG")
      (description "SWITCH TACTILE SPST-NO 0.05A 12V")
      (fields (field (name "MANUFACTURER") "ITT C&K"))
      (libsource (lib "Schlib") (part "PTS645SH50SMTR92LFS"))
    )
    (comp (ref "SW2")
      (value "PTS645SH50SMTR92LFS")
      (footprint "FP-PTS645SH50SMTR92LFS-MFG")
      (description "SWITCH TACTILE SPST-NO 0.05A 12V")
      (fields (field (name "MANUFACTURER") "ITT C&K"))
      (libsource (lib "Schlib") (part "PTS645SH50SMTR92LFS"))
    )
    (comp (ref "X1")
      (value "TSX-322524.0000MF15X-AC0")
      (footprint "TSX3225240000MF15XAC0")
      (description "24 MHz +/-10ppm Crystal 9pF 40 Ohms 4-SMD, No Lead")
      (libsource (lib "TSX-322524.0000MF15X-AC0") (part "TSX-322524.0000MF15X-AC0"))
    )
    (comp (ref "Y1")
      (value "XTAL")
      (footprint "R38")
      (description "Crystal Oscillator")
      (fields (field (name "PUBLISHER") "Altium Limited"))
      (libsource (lib "Miscellaneous Devices") (part "XTAL"))
    )
  )
  (nets
    (net (code "1") (name "+3V3") (class "Default")
      (node (ref "B1") (pin "1") (pinfunction "VBAT_1") (pintype "passive"))
      (node (ref "B1") (pin "24") (pinfunction "VDD_1_24") (pintype "passive"))
      (node (ref "B1") (pin "36") (pinfunction "VDD_2_36") (pintype "passive"))
      (node (ref "B1") (pin "48") (pinfunction "VDD_3_48") (pintype "passive"))
      (node (ref "B1") (pin "9") (pinfunction "VDDA/VREF+_9") (pintype "passive"))
      (node (ref "B2") (pin "8") (pinfunction "VCC_8") (pintype "passive"))
      (node (ref "B3") (pin "5") (pinfunction "FB_5") (pintype "passive"))
      (node (ref "C1") (pin "2") (pinfunction "2_2") (pintype "passive"))
      (node (ref "C10") (pin "2") (pinfunction "2_2") (pintype "passive"))
      (node (ref "C11") (pin "2") (pinfunction "2_2") (pintype "passive"))
      (node (ref "C15") (pin "2") (pinfunction "2_2") (pintype "passive"))
      (node (ref "C2") (pin "2") (pinfunction "2_2") (pintype "passive"))
      (node (ref "C20") (pin "2") (pinfunction "2_2") (pintype "passive"))
      (node (ref "C5") (pin "2") (pinfunction "2_2") (pintype "passive"))
      (node (ref "C6") (pin "2") (pinfunction "2_2") (pintype "passive"))
      (node (ref "C7") (pin "2") (pinfunction "2_2") (pintype "passive"))
      (node (ref "C8") (pin "2") (pinfunction "2_2") (pintype "passive"))
      (node (ref "C9") (pin "2") (pinfunction "2_2") (pintype "passive"))
      (node (ref "IC1") (pin "2") (pinfunction "3V3_2") (pintype "bidirectional"))
      (node (ref "IC2") (pin "8") (pinfunction "VDD_8") (pintype "bidirectional"))
      (node (ref "J1") (pin "1") (pinfunction "VCC_1") (pintype "passive"))
      (node (ref "L1") (pin "1") (pinfunction "1_1") (pintype "passive"))
      (node (ref "P1") (pin "1") (pinfunction "1_1") (pintype "passive"))
      (node (ref "P2") (pin "1") (pinfunction "1_1") (pintype "passive"))
      (node (ref "R1") (pin "2") (pinfunction "2_2") (pintype "passive"))
      (node (ref "R11") (pin "2") (pinfunction "2_2") (pintype "passive"))
      (node (ref "R14") (pin "1") (pinfunction "1_1") (pintype "passive"))
      (node (ref "R15") (pin "1") (pinfunction "1_1") (pintype "passive"))
      (node (ref "R2") (pin "1") (pinfunction "1_1") (pintype "passive"))
      (node (ref "R25") (pin "1") (pinfunction "1_1") (pintype "passive"))
      (node (ref "R26") (pin "1") (pinfunction "1_1") (pintype "passive"))
      (node (ref "R3") (pin "1") (pinfunction "1_1") (pintype "passive"))
      (node (ref "R6") (pin "2") (pinfunction "2_2") (pintype "passive"))
      (node (ref "R7") (pin "1") (pinfunction "1_1") (pintype "passive"))
      (node (ref "R8") (pin "2") (pinfunction "2_2") (pintype "passive"))
      (node (ref "R9") (pin "2") (pinfunction "2_2") (pintype "passive"))
    )
    (net (code "2") (name "+5V") (class "Default")
      (node (ref "B4") (pin "1") (pinfunction "VCC_1") (pintype "passive"))
      (node (ref "C16") (pin "2") (pinfunction "2_2") (pintype "passive"))
      (node (ref "R13") (pin "1") (pinfunction "1_1") (pintype "passive"))
    )
    (net (code "3") (name "+5V_VBUS1") (class "Default")
      (node (ref "C17") (pin "1") (pinfunction "1_1") (pintype "passive"))
      (node (ref "D9") (pin "2") (pinfunction "2_2") (pintype "passive"))
      (node (ref "J3") (pin "A4B9") (pinfunction "VBUS_A4B9_A4B9") (pintype "passive"))
      (node (ref "J3") (pin "B4A9") (pinfunction "VBUS_B4_B4A9") (pintype "passive"))
      (node (ref "R19") (pin "2") (pinfunction "2_2") (pintype "passive"))
    )
    (net (code "4") (name "/+VCC_FTDI") (class "Default")
      (node (ref "B5") (pin "12") (pinfunction "VCC_12") (pintype "passive"))
      (node (ref "C24") (pin "2") (pinfunction "2_2") (pintype "passive"))
      (node (ref "C25") (pin "1") (pinfunction "1_1") (pintype "passive"))
      (node (ref "R13") (pin "2") (pinfunction "2_2") (pintype "passive"))
      (node (ref "R14") (pin "2") (pinfunction "2_2") (pintype "passive"))
    )
    (net (code "5") (name "/3V3_FTDI") (class "Default")
      (node (ref "B5") (pin "10") (pinfunction "3V3OUT_10") (pintype "passive"))
      (node (ref "C26") (pin "1") (pinfunction "1_1") (pintype "passive"))
      (node (ref "C28") (pin "1") (pinfunction "1_1") (pintype "passive"))
      (node (ref "R15") (pin "2") (pinfunction "2_2") (pintype "passive"))
      (node (ref "R18") (pin "1") (pinfunction "1_1") (pintype "passive"))
    )
    (net (code "6") (name "/BOOT0") (class "Default")
      (node (ref "B1") (pin "44") (pinfunction "BOOT0_44") (pintype "passive"))
      (node (ref "C23") (pin "1") (pinfunction "1_1") (pintype "passive"))
      (node (ref "SW2") (pin "1") (pinfunction "1_1") (pintype "passive"))
      (node (ref "SW2") (pin "2") (pinfunction "2_2") (pintype "passive"))
    )
    (net (code "7") (name "/BTN_GPIO0") (class "Default")
      (node (ref "Q2") (pin "3") (pinfunction "C_3") (pintype "passive"))
      (node (ref "R27") (pin "1") (pinfunction "1_1") (pintype "passive"))
    )
    (net (code "8") (name "/CHIP_PU") (class "Default")
      (node (ref "C22") (pin "2") (pinfunction "2_2") (pintype "passive"))
      (node (ref "IC1") (pin "3") (pinfunction "EN_3") (pintype "bidirectional"))
      (node (ref "Q1") (pin "3") (pinfunction "C_3") (pintype "passive"))
      (node (ref "R1") (pin "1") (pinfunction "1_1") (pintype "passive"))
      (node (ref "R11") (pin "1") (pinfunction "1_1") (pintype "passive"))
      (node (ref "SW1") (pin "1") (pinfunction "1_1") (pintype "passive"))
      (node (ref "SW1") (pin "2") (pinfunction "2_2") (pintype "passive"))
    )
    (net (code "9") (name "/CON1_USB_N") (class "Default")
      (node (ref "D7") (pin "2") (pinfunction "2_2") (pintype "passive"))
      (node (ref "J3") (pin "A7") (pinfunction "Dn1_A7_A7") (pintype "passive"))
      (node (ref "J3") (pin "B7") (pinfunction "Dn2_B7_B7") (pintype "passive"))
      (node (ref "R16") (pin "1") (pinfunction "1_1") (pintype "passive"))
    )
    (net (code "10") (name "/CON1_USB_P") (class "Default")
      (node (ref "D8") (pin "2") (pinfunction "2_2") (pintype "passive"))
      (node (ref "J3") (pin "A6") (pinfunction "Dp1_A6_A6") (pintype "passive"))
      (node (ref "J3") (pin "B6") (pinfunction "Dp2_B6_B6") (pintype "passive"))
      (node (ref "R17") (pin "1") (pinfunction "1_1") (pintype "passive"))
    )
    (net (code "11") (name "/DTR_FTDI") (class "Default")
      (node (ref "B5") (pin "18") (pinfunction "DTR#_18") (pintype "passive"))
      (node (ref "Q2") (pin "2") (pinfunction "E_2") (pintype "passive"))
      (node (ref "R28") (pin "1") (pinfunction "1_1") (pintype "passive"))
    )
    (net (code "12") (name "/FTDI_RESET") (class "Default")
      (node (ref "B5") (pin "11") (pinfunction "RESET#_11") (pintype "passive"))
      (node (ref "C27") (pin "1") (pinfunction "1_1") (pintype "passive"))
      (node (ref "R18") (pin "2") (pinfunction "2_2") (pintype "passive"))
    )
    (net (code "13") (name "/FTDI_USB_N") (class "Default")
      (node (ref "B5") (pin "9") (pinfunction "USBDM_9") (pintype "passive"))
      (node (ref "R16") (pin "2") (pinfunction "2_2") (pintype "passive"))
    )
    (net (code "14") (name "/FTDI_USB_P") (class "Default")
      (node (ref "B5") (pin "8") (pinfunction "USBDP_8") (pintype "passive"))
      (node (ref "R17") (pin "2") (pinfunction "2_2") (pintype "passive"))
    )
    (net (code "15") (name "/GPIOA0") (class "Default")
      (node (ref "B1") (pin "10") (pinfunction "PA0_10") (pintype "passive"))
      (node (ref "P1") (pin "2") (pinfunction "2_2") (pintype "passive"))
    )
    (net (code "16") (name "/GPIOA1") (class "Default")
      (node (ref "B1") (pin "11") (pinfunction "PA1_11") (pintype "passive"))
      (node (ref "P1") (pin "3") (pinfunction "3_3") (pintype "passive"))
    )
    (net (code "17") (name "/GPIOA2{slash}TX2") (class "Default")
      (node (ref "B1") (pin "12") (pinfunction "PA2_12") (pintype "passive"))
      (node (ref "P1") (pin "4") (pinfunction "4_4") (pintype "passive"))
    )
    (net (code "18") (name "/GPIOA3{slash}RX2") (class "Default")
      (node (ref "B1") (pin "13") (pinfunction "PA3_13") (pintype "passive"))
      (node (ref "P1") (pin "5") (pinfunction "5_5") (pintype "passive"))
    )
    (net (code "19") (name "/GPIOA4") (class "Default")
      (node (ref "B1") (pin "14") (pinfunction "PA4_14") (pintype "passive"))
      (node (ref "P1") (pin "6") (pinfunction "6_6") (pintype "passive"))
    )
    (net (code "20") (name "/GPIOA5{slash}SCK1") (class "Default")
      (node (ref "B1") (pin "15") (pinfunction "PA5_15") (pintype "passive"))
      (node (ref "D4") (pin "2") (pinfunction "2_2") (pintype "passive"))
      (node (ref "IC2") (pin "6") (pinfunction "SCK_6") (pintype "bidirectional"))
      (node (ref "P1") (pin "7") (pinfunction "7_7") (pintype "passive"))
    )
    (net (code "21") (name "/GPIOA6{slash}MISO1") (class "Default")
      (node (ref "B1") (pin "16") (pinfunction "PA6_16") (pintype "passive"))
      (node (ref "D6") (pin "2") (pinfunction "2_2") (pintype "passive"))
      (node (ref "IC2") (pin "2") (pinfunction "SO/SIO1_2") (pintype "bidirectional"))
      (node (ref "P1") (pin "8") (pinfunction "8_8") (pintype "passive"))
    )
    (net (code "22") (name "/GPIOA7{slash}MOSI1") (class "Default")
      (node (ref "B1") (pin "17") (pinfunction "PA7_17") (pintype "passive"))
      (node (ref "D5") (pin "2") (pinfunction "2_2") (pintype "passive"))
      (node (ref "IC2") (pin "5") (pinfunction "SI/SIO0_5") (pintype "bidirectional"))
      (node (ref "P1") (pin "9") (pinfunction "9_9") (pintype "passive"))
    )
    (net (code "23") (name "/GPIOA8{slash}SCL3") (class "Default")
      (node (ref "B1") (pin "29") (pinfunction "PA8_29") (pintype "passive"))
      (node (ref "B2") (pin "6") (pinfunction "SCL_6") (pintype "passive"))
      (node (ref "R26") (pin "2") (pinfunction "2_2") (pintype "passive"))
    )
    (net (code "24") (name "/GPIOB0") (class "Default")
      (node (ref "B1") (pin "18") (pinfunction "PB0_18") (pintype "passive"))
      (node (ref "P2") (pin "2") (pinfunction "2_2") (pintype "passive"))
    )
    (net (code "25") (name "/GPIOB1") (class "Default")
      (node (ref "B1") (pin "19") (pinfunction "PB1_19") (pintype "passive"))
      (node (ref "P2") (pin "3") (pinfunction "3_3") (pintype "passive"))
    )
    (net (code "26") (name "/GPIOB2") (class "Default")
      (node (ref "B1") (pin "20") (pinfunction "PB2_20") (pintype "passive"))
      (node (ref "P2") (pin "4") (pinfunction "4_4") (pintype "passive"))
    )
    (net (code "27") (name "/GPIOB4{slash}SDA3") (class "Default")
      (node (ref "B1") (pin "40") (pinfunction "PB4_40") (pintype "passive"))
      (node (ref "B2") (pin "5") (pinfunction "SDA_5") (pintype "passive"))
    )
    (net (code "28") (name "/GPIOB5") (class "Default")
      (node (ref "B1") (pin "41") (pinfunction "PB5_41") (pintype "passive"))
      (node (ref "P2") (pin "5") (pinfunction "5_5") (pintype "passive"))
      (node (ref "R25") (pin "2") (pinfunction "2_2") (pintype "passive"))
    )
    (net (code "29") (name "/GPIOB6{slash}SCL1") (class "Default")
      (node (ref "B1") (pin "42") (pinfunction "PB6_42") (pintype "passive"))
      (node (ref "P2") (pin "6") (pinfunction "6_6") (pintype "passive"))
      (node (ref "R3") (pin "2") (pinfunction "2_2") (pintype "passive"))
    )
    (net (code "30") (name "/GPIOB7{slash}SDA1") (class "Default")
      (node (ref "B1") (pin "43") (pinfunction "PB7_43") (pintype "passive"))
      (node (ref "P2") (pin "7") (pinfunction "7_7") (pintype "passive"))
      (node (ref "R2") (pin "2") (pinfunction "2_2") (pintype "passive"))
    )
    (net (code "31") (name "/GPIOB8") (class "Default")
      (node (ref "B1") (pin "45") (pinfunction "PB8_45") (pintype "passive"))
      (node (ref "P2") (pin "8") (pinfunction "8_8") (pintype "passive"))
    )
    (net (code "32") (name "/GPIOB9") (class "Default")
      (node (ref "B1") (pin "46") (pinfunction "PB9_46") (pintype "passive"))
      (node (ref "P2") (pin "9") (pinfunction "9_9") (pintype "passive"))
    )
    (net (code "33") (name "/LED Anode") (class "Default")
      (node (ref "B1") (pin "26") (pinfunction "PB13_26") (pintype "passive"))
      (node (ref "D1") (pin "2") (pinfunction "2_2") (pintype "passive"))
    )
    (net (code "34") (name "/LED Cathode") (class "Default")
      (node (ref "D1") (pin "1") (pinfunction "1_1") (pintype "passive"))
      (node (ref "R5") (pin "2") (pinfunction "2_2") (pintype "passive"))
    )
    (net (code "35") (name "/MCU OSC IN") (class "Default")
      (node (ref "B1") (pin "5") (pinfunction "PH0-OSC_IN_5") (pintype "passive"))
      (node (ref "C12") (pin "2") (pinfunction "2_2") (pintype "passive"))
      (node (ref "X1") (pin "1") (pinfunction "CRYSTAL_1_1") (pintype "passive"))
    )
    (net (code "36") (name "/MCU OSC OUT") (class "Default")
      (node (ref "B1") (pin "6") (pinfunction "PH0-OSC_OUT_6") (pintype "passive"))
      (node (ref "C13") (pin "2") (pinfunction "2_2") (pintype "passive"))
      (node (ref "X1") (pin "3") (pinfunction "CRYSTAL_2_3") (pintype "passive"))
    )
    (net (code "37") (name "/NRST") (class "Default")
      (node (ref "B1") (pin "7") (pinfunction "NRST_7") (pintype "passive"))
      (node (ref "C18") (pin "2") (pinfunction "2_2") (pintype "passive"))
      (node (ref "J1") (pin "3") (pinfunction "NRST_3") (pintype "passive"))
      (node (ref "R6") (pin "1") (pinfunction "1_1") (pintype "passive"))
    )
    (net (code "38") (name "/RTS_FTDI") (class "Default")
      (node (ref "B5") (pin "19") (pinfunction "RTS#_19") (pintype "passive"))
      (node (ref "Q1") (pin "2") (pinfunction "E_2") (pintype "passive"))
      (node (ref "R29") (pin "1") (pinfunction "1_1") (pintype "passive"))
    )
    (net (code "39") (name "/RXD_FTDI") (class "Default")
      (node (ref "B5") (pin "1") (pinfunction "RXD_1") (pintype "passive"))
      (node (ref "IC1") (pin "26") (pinfunction "IO4_26") (pintype "bidirectional"))
    )
    (net (code "40") (name "/SWCLK") (class "Default")
      (node (ref "B1") (pin "37") (pinfunction "PA14_37") (pintype "passive"))
      (node (ref "B1") (pin "38") (pinfunction "PA15_38") (pintype "passive"))
      (node (ref "J1") (pin "4") (pinfunction "SWCLK/TCK_4") (pintype "passive"))
    )
    (net (code "41") (name "/SWDIO") (class "Default")
      (node (ref "B1") (pin "34") (pinfunction "PA13_34") (pintype "passive"))
      (node (ref "J1") (pin "2") (pinfunction "SWDIO/TMS_2") (pintype "passive"))
    )
    (net (code "42") (name "/SWO") (class "Default")
      (node (ref "B1") (pin "39") (pinfunction "PB3_39") (pintype "passive"))
      (node (ref "J1") (pin "6") (pinfunction "SWO/TDO_6") (pintype "passive"))
    )
    (net (code "43") (name "/TXD_FTDI") (class "Default")
      (node (ref "B5") (pin "17") (pinfunction "TXD_17") (pintype "passive"))
      (node (ref "IC1") (pin "29") (pinfunction "IO5_29") (pintype "bidirectional"))
    )
    (net (code "44") (name "/USART_RX1") (class "Default")
      (node (ref "B1") (pin "31") (pinfunction "PA10_31") (pintype "passive"))
      (node (ref "IC1") (pin "35") (pinfunction "TXD0_35") (pintype "bidirectional"))
    )
    (net (code "45") (name "/USART_TX1") (class "Default")
      (node (ref "B1") (pin "30") (pinfunction "PA9_30") (pintype "passive"))
      (node (ref "IC1") (pin "34") (pinfunction "RXD0_34") (pintype "bidirectional"))
    )
    (net (code "46") (name "/USB_D_N") (class "Default")
      (node (ref "B1") (pin "32") (pinfunction "PA11_32") (pintype "passive"))
      (node (ref "B4") (pin "6") (pinfunction "IO2_6") (pintype "passive"))
    )
    (net (code "47") (name "/USB_D_P") (class "Default")
      (node (ref "B1") (pin "33") (pinfunction "PA12_33") (pintype "passive"))
      (node (ref "B4") (pin "3") (pinfunction "IO1_3") (pintype "passive"))
      (node (ref "D10") (pin "2") (pinfunction "2_2") (pintype "passive"))
      (node (ref "J2") (pin "A7") (pinfunction "Dn1_A7_A7") (pintype "passive"))
      (node (ref "J2") (pin "B7") (pinfunction "Dn2_B7_B7") (pintype "passive"))
    )
    (net (code "48") (name "/VCAP1") (class "Default")
      (node (ref "B1") (pin "22") (pinfunction "VCAP_1_22") (pintype "passive"))
      (node (ref "C19") (pin "2") (pinfunction "2_2") (pintype "passive"))
    )
    (net (code "49") (name "GND") (class "Default")
      (node (ref "B1") (pin "23") (pinfunction "VSS_1_23") (pintype "passive"))
      (node (ref "B1") (pin "35") (pinfunction "VSS_2_35") (pintype "passive"))
      (node (ref "B1") (pin "47") (pinfunction "VSS_3_47") (pintype "passive"))
      (node (ref "B1") (pin "8") (pinfunction "VSSA/VREF-_8") (pintype "passive"))
      (node (ref "B2") (pin "4") (pinfunction "GND_4") (pintype "passive"))
      (node (ref "B2") (pin "9") (pinfunction "EP_9") (pintype "passive"))
      (node (ref "B3") (pin "2") (pinfunction "GND_2") (pintype "passive"))
      (node (ref "B4") (pin "4") (pinfunction "GND_1_4") (pintype "passive"))
      (node (ref "B4") (pin "7") (pinfunction "GND_2_7") (pintype "passive"))
      (node (ref "B5") (pin "13") (pinfunction "GND_2_13") (pintype "passive"))
      (node (ref "B5") (pin "3") (pinfunction "GND_1_3") (pintype "passive"))
      (node (ref "C1") (pin "1") (pinfunction "1_1") (pintype "passive"))
      (node (ref "C10") (pin "1") (pinfunction "1_1") (pintype "passive"))
      (node (ref "C11") (pin "1") (pinfunction "1_1") (pintype "passive"))
      (node (ref "C12") (pin "1") (pinfunction "1_1") (pintype "passive"))
      (node (ref "C13") (pin "1") (pinfunction "1_1") (pintype "passive"))
      (node (ref "C14") (pin "1") (pinfunction "1_1") (pintype "passive"))
      (node (ref "C15") (pin "1") (pinfunction "1_1") (pintype "passive"))
      (node (ref "C16") (pin "1") (pinfunction "1_1") (pintype "passive"))
      (node (ref "C17") (pin "2") (pinfunction "2_2") (pintype "passive"))
      (node (ref "C18") (pin "1") (pinfunction "1_1") (pintype "passive"))
      (node (ref "C19") (pin "1") (pinfunction "1_1") (pintype "passive"))
      (node (ref "C2") (pin "1") (pinfunction "1_1") (pintype "passive"))
      (node (ref "C20") (pin "1") (pinfunction "1_1") (pintype "passive"))
      (node (ref "C21") (pin "1") (pinfunction "1_1") (pintype "passive"))
      (node (ref "C22") (pin "1") (pinfunction "1_1") (pintype "passive"))
      (node (ref "C23") (pin "2") (pinfunction "2_2") (pintype "passive"))
      (node (ref "C24") (pin "1") (pinfunction "1_1") (pintype "passive"))
      (node (ref "C25") (pin "2") (pinfunction "2_2") (pintype "passive"))
      (node (ref "C26") (pin "2") (pinfunction "2_2") (pintype "passive"))
      (node (ref "C27") (pin "2") (pinfunction "2_2") (pintype "passive"))
      (node (ref "C28") (pin "2") (pinfunction "2_2") (pintype "passive"))
      (node (ref "C29") (pin "2") (pinfunction "2_2") (pintype "passive"))
      (node (ref "C3") (pin "2") (pinfunction "2_2") (pintype "passive"))
      (node (ref "C4") (pin "2") (pinfunction "2_2") (pintype "passive"))
      (node (ref "C5") (pin "1") (pinfunction "1_1") (pintype "passive"))
      (node (ref "C6") (pin "1") (pinfunction "1_1") (pintype "passive"))
      (node (ref "C7") (pin "1") (pinfunction "1_1") (pintype "passive"))
      (node (ref "C8") (pin "1") (pinfunction "1_1") (pintype "passive"))
      (node (ref "C9") (pin "1") (pinfunction "1_1") (pintype "passive"))
      (node (ref "D10") (pin "1") (pinfunction "1_1") (pintype "passive"))
      (node (ref "D11") (pin "1") (pinfunction "1_1") (pintype "passive"))
      (node (ref "D12") (pin "1") (pinfunction "1_1") (pintype "passive"))
      (node (ref "D2") (pin "2") (pinfunction "K_2") (pintype "passive"))
      (node (ref "D3") (pin "1") (pinfunction "1_1") (pintype "passive"))
      (node (ref "D6") (pin "1") (pinfunction "1_1") (pintype "passive"))
      (node (ref "D7") (pin "1") (pinfunction "1_1") (pintype "passive"))
      (node (ref "D8") (pin "1") (pinfunction "1_1") (pintype "passive"))
      (node (ref "D9") (pin "1") (pinfunction "1_1") (pintype "passive"))
      (node (ref "IC1") (pin "1") (pinfunction "GND_1") (pintype "bidirectional"))
      (node (ref "IC1") (pin "15") (pinfunction "GND_15") (pintype "bidirectional"))
      (node (ref "IC1") (pin "38") (pinfunction "GND_38") (pintype "bidirectional"))
      (node (ref "IC1") (pin "39") (pinfunction "GND_39") (pintype "bidirectional"))
      (node (ref "IC1") (pin "40") (pinfunction "GND_40") (pintype "bidirectional"))
      (node (ref "IC1") (pin "41") (pinfunction "GND_41") (pintype "bidirectional"))
      (node (ref "IC1") (pin "42") (pinfunction "GND_42") (pintype "bidirectional"))
      (node (ref "IC1") (pin "43") (pinfunction "GND_43") (pintype "bidirectional"))
      (node (ref "IC1") (pin "44") (pinfunction "GND_44") (pintype "bidirectional"))
      (node (ref "IC1") (pin "45") (pinfunction "GND_45") (pintype "bidirectional"))
      (node (ref "IC1") (pin "46") (pinfunction "GND_46") (pintype "bidirectional"))
      (node (ref "IC1") (pin "47") (pinfunction "GND_47") (pintype "bidirectional"))
      (node (ref "IC2") (pin "1") (pinfunction "CE#_1") (pintype "bidirectional"))
      (node (ref "IC2") (pin "4") (pinfunction "VSS_4") (pintype "bidirectional"))
      (node (ref "IC2") (pin "7") (pinfunction "HOLD#_7") (pintype "bidirectional"))
      (node (ref "IC2") (pin "9") (pinfunction "EP_9") (pintype "bidirectional"))
      (node (ref "J1") (pin "5") (pinfunction "GND_5") (pintype "passive"))
      (node (ref "J2") (pin "A1B12") (pinfunction "GND_A1B12_A1B12") (pintype "passive"))
      (node (ref "J2") (pin "B1A12") (pinfunction "GND_B1_B1A12") (pintype "passive"))
      (node (ref "J2") (pin "S1") (pinfunction "SHIELD_1_S1") (pintype "passive"))
      (node (ref "J2") (pin "S2") (pinfunction "SHIELD_2_S2") (pintype "passive"))
      (node (ref "J2") (pin "S3") (pinfunction "SHIELD_3_S3") (pintype "passive"))
      (node (ref "J2") (pin "S4") (pinfunction "SHIELD_4_S4") (pintype "passive"))
      (node (ref "J3") (pin "A1B12") (pinfunction "GND_A1B12_A1B12") (pintype "passive"))
      (node (ref "J3") (pin "B1A12") (pinfunction "GND_B1_B1A12") (pintype "passive"))
      (node (ref "J3") (pin "S1") (pinfunction "SHIELD_1_S1") (pintype "passive"))
      (node (ref "J3") (pin "S2") (pinfunction "SHIELD_2_S2") (pintype "passive"))
      (node (ref "J3") (pin "S3") (pinfunction "SHIELD_3_S3") (pintype "passive"))
      (node (ref "J3") (pin "S4") (pinfunction "SHIELD_4_S4") (pintype "passive"))
      (node (ref "P1") (pin "10") (pinfunction "10_10") (pintype "passive"))
      (node (ref "P2") (pin "10") (pinfunction "10_10") (pintype "passive"))
      (node (ref "R10") (pin "2") (pinfunction "2_2") (pintype "passive"))
      (node (ref "R12") (pin "2") (pinfunction "2_2") (pintype "passive"))
      (node (ref "R20") (pin "2") (pinfunction "2_2") (pintype "passive"))
      (node (ref "R21") (pin "2") (pinfunction "2_2") (pintype "passive"))
      (node (ref "R22") (pin "1") (pinfunction "1_1") (pintype "passive"))
      (node (ref "R23") (pin "2") (pinfunction "2_2") (pintype "passive"))
      (node (ref "R5") (pin "1") (pinfunction "1_1") (pintype "passive"))
      (node (ref "S1") (pin "3") (pinfunction "3_3") (pintype "passive"))
      (node (ref "SW1") (pin "3") (pinfunction "3_3") (pintype "passive"))
      (node (ref "SW1") (pin "4") (pinfunction "4_4") (pintype "passive"))
      (node (ref "SW2") (pin "3") (pinfunction "3_3") (pintype "passive"))
      (node (ref "SW2") (pin "4") (pinfunction "4_4") (pintype "passive"))
      (node (ref "X1") (pin "2") (pinfunction "GROUND_1_2") (pintype "passive"))
      (node (ref "X1") (pin "4") (pinfunction "GROUND_2_4") (pintype "passive"))
    )
    (net (code "50") (name "Net-(B3-EN)") (class "Default")
      (node (ref "B3") (pin "1") (pinfunction "EN_1") (pintype "passive"))
      (node (ref "R24") (pin "1") (pinfunction "1_1") (pintype "passive"))
    )
    (net (code "51") (name "Net-(B3-SW)") (class "Default")
      (node (ref "B3") (pin "3") (pinfunction "SW_3") (pintype "passive"))
      (node (ref "L1") (pin "2") (pinfunction "2_2") (pintype "passive"))
    )
    (net (code "52") (name "Net-(B5-CBUS0)") (class "Default")
      (node (ref "B5") (pin "15") (pinfunction "CBUS0_15") (pintype "passive"))
      (node (ref "R23") (pin "1") (pinfunction "1_1") (pintype "passive"))
    )
    (net (code "53") (name "Net-(B5-CBUS3)") (class "Default")
      (node (ref "B5") (pin "16") (pinfunction "CBUS3_16") (pintype "passive"))
      (node (ref "R22") (pin "2") (pinfunction "2_2") (pintype "passive"))
    )
    (net (code "54") (name "Net-(D2-A)") (class "Default")
      (node (ref "D2") (pin "1") (pinfunction "A_1") (pintype "passive"))
      (node (ref "R7") (pin "2") (pinfunction "2_2") (pintype "passive"))
    )
    (net (code "55") (name "Net-(D3-Pad2)") (class "Default")
      (node (ref "D3") (pin "2") (pinfunction "2_2") (pintype "passive"))
      (node (ref "R9") (pin "1") (pinfunction "1_1") (pintype "passive"))
    )
    (net (code "56") (name "Net-(IC1-IO0)") (class "Default")
      (node (ref "IC1") (pin "25") (pinfunction "IO0_25") (pintype "bidirectional"))
      (node (ref "R27") (pin "2") (pinfunction "2_2") (pintype "passive"))
    )
    (net (code "57") (name "Net-(IC1-IO32)") (class "Default")
      (node (ref "C3") (pin "1") (pinfunction "1_1") (pintype "passive"))
      (node (ref "IC1") (pin "8") (pinfunction "IO32_8") (pintype "bidirectional"))
      (node (ref "R4") (pin "2") (pinfunction "2_2") (pintype "passive"))
      (node (ref "Y1") (pin "1") (pinfunction "OSC1_1") (pintype "passive"))
    )
    (net (code "58") (name "Net-(IC1-IO33)") (class "Default")
      (node (ref "C4") (pin "1") (pinfunction "1_1") (pintype "passive"))
      (node (ref "IC1") (pin "9") (pinfunction "IO33_9") (pintype "bidirectional"))
      (node (ref "R4") (pin "1") (pinfunction "1_1") (pintype "passive"))
      (node (ref "Y1") (pin "2") (pinfunction "OSC2_2") (pintype "passive"))
    )
    (net (code "59") (name "Net-(IC1-NC-Pad17)") (class "Default")
      (node (ref "IC1") (pin "17") (pinfunction "NC_17") (pintype "bidirectional"))
      (node (ref "IC1") (pin "18") (pinfunction "NC_18") (pintype "bidirectional"))
      (node (ref "IC1") (pin "19") (pinfunction "NC_19") (pintype "bidirectional"))
      (node (ref "IC1") (pin "20") (pinfunction "NC_20") (pintype "bidirectional"))
      (node (ref "IC1") (pin "21") (pinfunction "NC_21") (pintype "bidirectional"))
      (node (ref "IC1") (pin "22") (pinfunction "NC_22") (pintype "bidirectional"))
      (node (ref "IC1") (pin "32") (pinfunction "NC_32") (pintype "bidirectional"))
    )
    (net (code "60") (name "Net-(IC2-WP#)") (class "Default")
      (node (ref "C21") (pin "2") (pinfunction "2_2") (pintype "passive"))
      (node (ref "IC2") (pin "3") (pinfunction "WP#_3") (pintype "bidirectional"))
      (node (ref "S1") (pin "2") (pinfunction "2_2") (pintype "passive"))
    )
    (net (code "61") (name "Net-(J2-CC1_A5)") (class "Default")
      (node (ref "J2") (pin "A5") (pinfunction "CC1_A5_A5") (pintype "passive"))
      (node (ref "R12") (pin "1") (pinfunction "1_1") (pintype "passive"))
    )
    (net (code "62") (name "Net-(J2-CC2_B5)") (class "Default")
      (node (ref "J2") (pin "B5") (pinfunction "CC2_B5_B5") (pintype "passive"))
      (node (ref "R10") (pin "1") (pinfunction "1_1") (pintype "passive"))
    )
    (net (code "63") (name "Net-(J2-Dp1_A6)") (class "Default")
      (node (ref "D11") (pin "2") (pinfunction "2_2") (pintype "passive"))
      (node (ref "J2") (pin "A6") (pinfunction "Dp1_A6_A6") (pintype "passive"))
      (node (ref "J2") (pin "B6") (pinfunction "Dp2_B6_B6") (pintype "passive"))
    )
    (net (code "64") (name "Net-(J3-CC1_A5)") (class "Default")
      (node (ref "J3") (pin "A5") (pinfunction "CC1_A5_A5") (pintype "passive"))
      (node (ref "R21") (pin "1") (pinfunction "1_1") (pintype "passive"))
    )
    (net (code "65") (name "Net-(J3-CC2_B5)") (class "Default")
      (node (ref "J3") (pin "B5") (pinfunction "CC2_B5_B5") (pintype "passive"))
      (node (ref "R20") (pin "1") (pinfunction "1_1") (pintype "passive"))
    )
    (net (code "66") (name "Net-(Q1-B)") (class "Default")
      (node (ref "Q1") (pin "1") (pinfunction "B_1") (pintype "passive"))
      (node (ref "R28") (pin "2") (pinfunction "2_2") (pintype "passive"))
    )
    (net (code "67") (name "Net-(Q2-B)") (class "Default")
      (node (ref "Q2") (pin "1") (pinfunction "B_1") (pintype "passive"))
      (node (ref "R29") (pin "2") (pinfunction "2_2") (pintype "passive"))
    )
    (net (code "68") (name "Net-(R8-Pad1)") (class "Default")
      (node (ref "R8") (pin "1") (pinfunction "1_1") (pintype "passive"))
      (node (ref "S1") (pin "1") (pinfunction "1_1") (pintype "passive"))
    )
    (net (code "69") (name "VBUS") (class "Default")
      (node (ref "B3") (pin "4") (pinfunction "VIN_4") (pintype "passive"))
      (node (ref "C14") (pin "2") (pinfunction "2_2") (pintype "passive"))
      (node (ref "C29") (pin "1") (pinfunction "1_1") (pintype "passive"))
      (node (ref "D12") (pin "2") (pinfunction "2_2") (pintype "passive"))
      (node (ref "J2") (pin "A4B9") (pinfunction "VBUS_A4B9_A4B9") (pintype "passive"))
      (node (ref "J2") (pin "B4A9") (pinfunction "VBUS_B4_B4A9") (pintype "passive"))
      (node (ref "R24") (pin "2") (pinfunction "2_2") (pintype "passive"))
    )
    (net (code "70") (name "unconnected-(B1-PB10-Pad21)") (class "Default")
      (node (ref "B1") (pin "21") (pinfunction "PB10_21") (pintype "passive"))
    )
    (net (code "71") (name "unconnected-(B1-PB12-Pad25)") (class "Default")
      (node (ref "B1") (pin "25") (pinfunction "PB12_25") (pintype "passive"))
    )
    (net (code "72") (name "unconnected-(B1-PB14-Pad27)") (class "Default")
      (node (ref "B1") (pin "27") (pinfunction "PB14_27") (pintype "passive+no_connect"))
    )
    (net (code "73") (name "unconnected-(B1-PB15-Pad28)") (class "Default")
      (node (ref "B1") (pin "28") (pinfunction "PB15_28") (pintype "passive+no_connect"))
    )
    (net (code "74") (name "unconnected-(B1-PC13-Pad2)") (class "Default")
      (node (ref "B1") (pin "2") (pinfunction "PC13_2") (pintype "passive+no_connect"))
    )
    (net (code "75") (name "unconnected-(B1-PC14-OSC32_IN-Pad3)") (class "Default")
      (node (ref "B1") (pin "3") (pinfunction "PC14-OSC32_IN_3") (pintype "passive+no_connect"))
    )
    (net (code "76") (name "unconnected-(B1-PC15-OSC32_OUT-Pad4)") (class "Default")
      (node (ref "B1") (pin "4") (pinfunction "PC15-OSC32_OUT_4") (pintype "passive+no_connect"))
    )
    (net (code "77") (name "unconnected-(B1-THERMAL_PAD-Pad49)") (class "Default")
      (node (ref "B1") (pin "49") (pinfunction "THERMAL_PAD_49") (pintype "passive"))
    )
    (net (code "78") (name "unconnected-(B2-NC_1-Pad1)") (class "Default")
      (node (ref "B2") (pin "1") (pinfunction "NC_1_1") (pintype "passive"))
    )
    (net (code "79") (name "unconnected-(B2-NC_2-Pad2)") (class "Default")
      (node (ref "B2") (pin "2") (pinfunction "NC_2_2") (pintype "passive"))
    )
    (net (code "80") (name "unconnected-(B2-NC_3-Pad3)") (class "Default")
      (node (ref "B2") (pin "3") (pinfunction "NC_3_3") (pintype "passive"))
    )
    (net (code "81") (name "unconnected-(B2-NC_4-Pad7)") (class "Default")
      (node (ref "B2") (pin "7") (pinfunction "NC_4_7") (pintype "passive"))
    )
    (net (code "82") (name "unconnected-(B4-N.C._1-Pad2)") (class "Default")
      (node (ref "B4") (pin "2") (pinfunction "N.C._1_2") (pintype "passive"))
    )
    (net (code "83") (name "unconnected-(B4-N.C._2-Pad5)") (class "Default")
      (node (ref "B4") (pin "5") (pinfunction "N.C._2_5") (pintype "passive"))
    )
    (net (code "84") (name "unconnected-(B5-CBUS1-Pad14)") (class "Default")
      (node (ref "B5") (pin "14") (pinfunction "CBUS1_14") (pintype "passive+no_connect"))
    )
    (net (code "85") (name "unconnected-(B5-CBUS2-Pad7)") (class "Default")
      (node (ref "B5") (pin "7") (pinfunction "CBUS2_7") (pintype "passive+no_connect"))
    )
    (net (code "86") (name "unconnected-(B5-CTS#-Pad6)") (class "Default")
      (node (ref "B5") (pin "6") (pinfunction "CTS#_6") (pintype "passive+no_connect"))
    )
    (net (code "87") (name "unconnected-(B5-DCD#-Pad5)") (class "Default")
      (node (ref "B5") (pin "5") (pinfunction "DCD#_5") (pintype "passive+no_connect"))
    )
    (net (code "88") (name "unconnected-(B5-DSR#-Pad4)") (class "Default")
      (node (ref "B5") (pin "4") (pinfunction "DSR#_4") (pintype "passive+no_connect"))
    )
    (net (code "89") (name "unconnected-(B5-EP-Pad21)") (class "Default")
      (node (ref "B5") (pin "21") (pinfunction "EP_21") (pintype "passive"))
    )
    (net (code "90") (name "unconnected-(B5-RI#-Pad2)") (class "Default")
      (node (ref "B5") (pin "2") (pinfunction "RI#_2") (pintype "passive+no_connect"))
    )
    (net (code "91") (name "unconnected-(B5-VCCIO-Pad20)") (class "Default")
      (node (ref "B5") (pin "20") (pinfunction "VCCIO_20") (pintype "passive"))
    )
    (net (code "92") (name "unconnected-(D4-Pad1)") (class "Default")
      (node (ref "D4") (pin "1") (pinfunction "1_1") (pintype "passive"))
    )
    (net (code "93") (name "unconnected-(D5-Pad1)") (class "Default")
      (node (ref "D5") (pin "1") (pinfunction "1_1") (pintype "passive"))
    )
    (net (code "94") (name "unconnected-(IC1-IO2-Pad24)") (class "Default")
      (node (ref "IC1") (pin "24") (pinfunction "IO2_24") (pintype "bidirectional+no_connect"))
    )
    (net (code "95") (name "unconnected-(IC1-IO12-Pad14)") (class "Default")
      (node (ref "IC1") (pin "14") (pinfunction "IO12_14") (pintype "bidirectional+no_connect"))
    )
    (net (code "96") (name "unconnected-(IC1-IO13-Pad16)") (class "Default")
      (node (ref "IC1") (pin "16") (pinfunction "IO13_16") (pintype "bidirectional+no_connect"))
    )
    (net (code "97") (name "unconnected-(IC1-IO14-Pad13)") (class "Default")
      (node (ref "IC1") (pin "13") (pinfunction "IO14_13") (pintype "bidirectional+no_connect"))
    )
    (net (code "98") (name "unconnected-(IC1-IO15-Pad23)") (class "Default")
      (node (ref "IC1") (pin "23") (pinfunction "IO15_23") (pintype "bidirectional+no_connect"))
    )
    (net (code "99") (name "unconnected-(IC1-IO16-Pad27)") (class "Default")
      (node (ref "IC1") (pin "27") (pinfunction "IO16_27") (pintype "bidirectional+no_connect"))
    )
    (net (code "100") (name "unconnected-(IC1-IO17-Pad28)") (class "Default")
      (node (ref "IC1") (pin "28") (pinfunction "IO17_28") (pintype "bidirectional+no_connect"))
    )
    (net (code "101") (name "unconnected-(IC1-IO18-Pad30)") (class "Default")
      (node (ref "IC1") (pin "30") (pinfunction "IO18_30") (pintype "bidirectional+no_connect"))
    )
    (net (code "102") (name "unconnected-(IC1-IO19-Pad31)") (class "Default")
      (node (ref "IC1") (pin "31") (pinfunction "IO19_31") (pintype "bidirectional+no_connect"))
    )
    (net (code "103") (name "unconnected-(IC1-IO21-Pad33)") (class "Default")
      (node (ref "IC1") (pin "33") (pinfunction "IO21_33") (pintype "bidirectional+no_connect"))
    )
    (net (code "104") (name "unconnected-(IC1-IO22-Pad36)") (class "Default")
      (node (ref "IC1") (pin "36") (pinfunction "IO22_36") (pintype "bidirectional+no_connect"))
    )
    (net (code "105") (name "unconnected-(IC1-IO23-Pad37)") (class "Default")
      (node (ref "IC1") (pin "37") (pinfunction "IO23_37") (pintype "bidirectional+no_connect"))
    )
    (net (code "106") (name "unconnected-(IC1-IO25-Pad10)") (class "Default")
      (node (ref "IC1") (pin "10") (pinfunction "IO25_10") (pintype "bidirectional+no_connect"))
    )
    (net (code "107") (name "unconnected-(IC1-IO26-Pad11)") (class "Default")
      (node (ref "IC1") (pin "11") (pinfunction "IO26_11") (pintype "bidirectional+no_connect"))
    )
    (net (code "108") (name "unconnected-(IC1-IO27-Pad12)") (class "Default")
      (node (ref "IC1") (pin "12") (pinfunction "IO27_12") (pintype "bidirectional+no_connect"))
    )
    (net (code "109") (name "unconnected-(IC1-IO34-Pad6)") (class "Default")
      (node (ref "IC1") (pin "6") (pinfunction "IO34_6") (pintype "bidirectional+no_connect"))
    )
    (net (code "110") (name "unconnected-(IC1-IO35-Pad7)") (class "Default")
      (node (ref "IC1") (pin "7") (pinfunction "IO35_7") (pintype "bidirectional+no_connect"))
    )
    (net (code "111") (name "unconnected-(IC1-SENSOR_VN-Pad5)") (class "Default")
      (node (ref "IC1") (pin "5") (pinfunction "SENSOR_VN_5") (pintype "bidirectional+no_connect"))
    )
    (net (code "112") (name "unconnected-(IC1-SENSOR_VP-Pad4)") (class "Default")
      (node (ref "IC1") (pin "4") (pinfunction "SENSOR_VP_4") (pintype "bidirectional+no_connect"))
    )
    (net (code "113") (name "unconnected-(J2-SBU1_A8-PadA8)") (class "Default")
      (node (ref "J2") (pin "A8") (pinfunction "SBU1_A8_A8") (pintype "passive+no_connect"))
    )
    (net (code "114") (name "unconnected-(J2-SBU_B8-PadB8)") (class "Default")
      (node (ref "J2") (pin "B8") (pinfunction "SBU_B8_B8") (pintype "passive+no_connect"))
    )
    (net (code "115") (name "unconnected-(J3-SBU1_A8-PadA8)") (class "Default")
      (node (ref "J3") (pin "A8") (pinfunction "SBU1_A8_A8") (pintype "passive+no_connect"))
    )
    (net (code "116") (name "unconnected-(J3-SBU_B8-PadB8)") (class "Default")
      (node (ref "J3") (pin "B8") (pinfunction "SBU_B8_B8") (pintype "passive+no_connect"))
    )
    (net (code "117") (name "unconnected-(R19-Pad1)") (class "Default")
      (node (ref "R19") (pin "1") (pinfunction "1_1") (pintype "passive"))
    )
  )
)
